# Origin_pi.net
KiCad netlist of a schematic drawn in Altium Designer
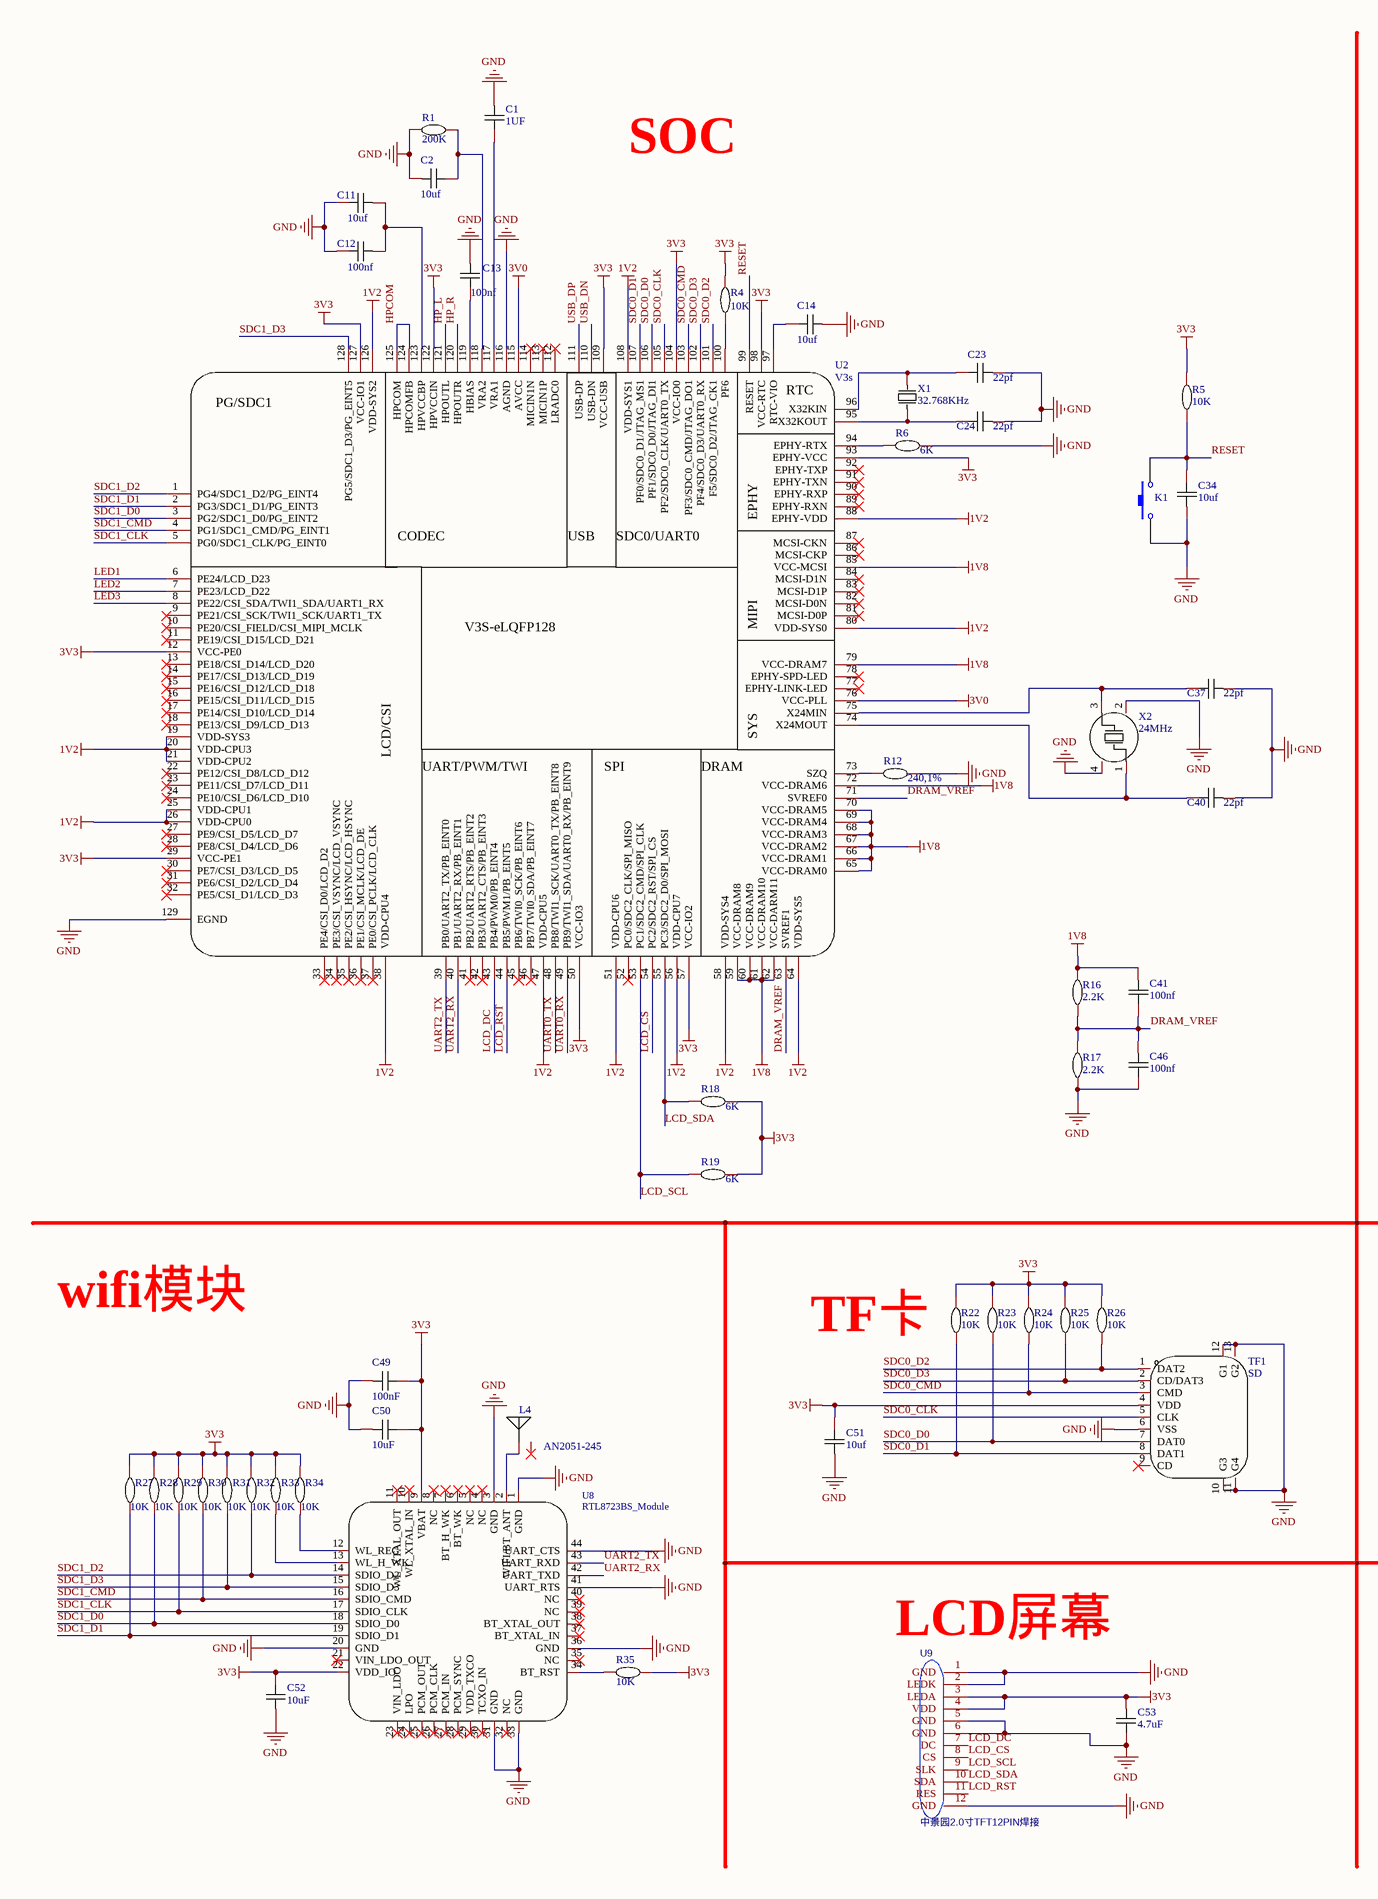
[diagram p0: Origin_pi.SchDoc, left]
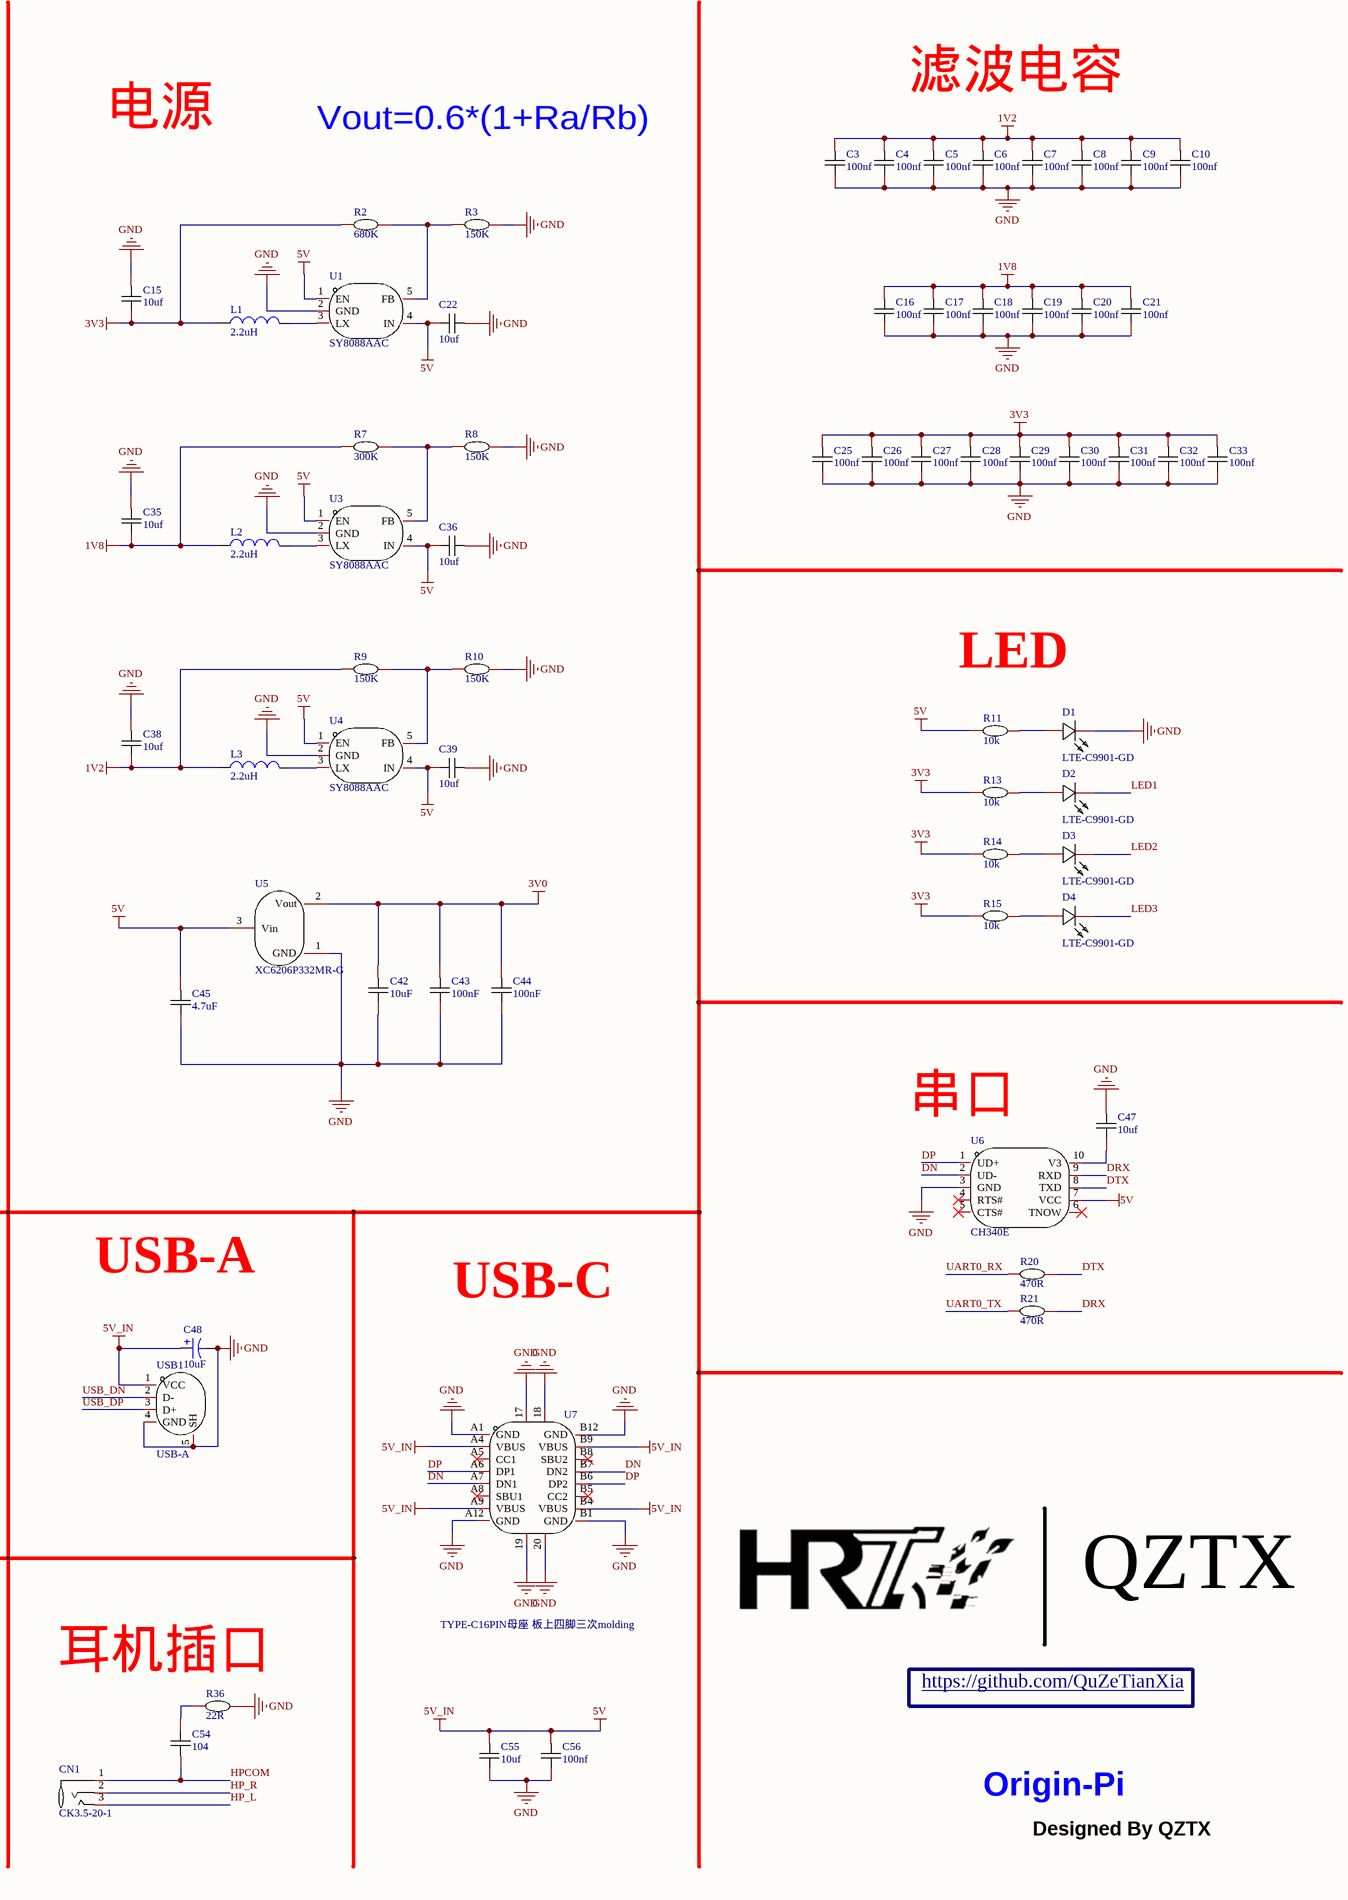
[diagram p1: Origin_pi.SchDoc, right]

(export (version "E")
  (design (tool "Eeschema 10.0.6"))
  (components
    (comp (ref "C1")
      (value "0603DS475K160NT")
      (footprint "C0603:PCBComponent_1")
      (fields (field (name "MANUFACTURER") "FH(风华)") (field (name "NAME") "1UF"))
      (libsource (lib "0603元件") (part "贴片电容0603"))
    )
    (comp (ref "C2")
      (value "0603DS475K160NT")
      (footprint "C0603:PCBComponent_1")
      (fields (field (name "MANUFACTURER") "FH(风华)") (field (name "NAME") "10uf"))
      (libsource (lib "0603元件") (part "贴片电容0603"))
    )
    (comp (ref "C3")
      (value "0603DS475K160NT")
      (footprint "C0603:PCBComponent_1")
      (fields (field (name "MANUFACTURER") "FH(风华)") (field (name "NAME") "100nf"))
      (libsource (lib "0603元件") (part "贴片电容0603"))
    )
    (comp (ref "C4")
      (value "0603DS475K160NT")
      (footprint "C0603:PCBComponent_1")
      (fields (field (name "MANUFACTURER") "FH(风华)") (field (name "NAME") "100nf"))
      (libsource (lib "0603元件") (part "贴片电容0603"))
    )
    (comp (ref "C5")
      (value "0603DS475K160NT")
      (footprint "C0603:PCBComponent_1")
      (fields (field (name "MANUFACTURER") "FH(风华)") (field (name "NAME") "100nf"))
      (libsource (lib "0603元件") (part "贴片电容0603"))
    )
    (comp (ref "C6")
      (value "0603DS475K160NT")
      (footprint "C0603:PCBComponent_1")
      (fields (field (name "MANUFACTURER") "FH(风华)") (field (name "NAME") "100nf"))
      (libsource (lib "0603元件") (part "贴片电容0603"))
    )
    (comp (ref "C7")
      (value "0603DS475K160NT")
      (footprint "C0603:PCBComponent_1")
      (fields (field (name "MANUFACTURER") "FH(风华)") (field (name "NAME") "100nf"))
      (libsource (lib "0603元件") (part "贴片电容0603"))
    )
    (comp (ref "C8")
      (value "0603DS475K160NT")
      (footprint "C0603:PCBComponent_1")
      (fields (field (name "MANUFACTURER") "FH(风华)") (field (name "NAME") "100nf"))
      (libsource (lib "0603元件") (part "贴片电容0603"))
    )
    (comp (ref "C9")
      (value "0603DS475K160NT")
      (footprint "C0603:PCBComponent_1")
      (fields (field (name "MANUFACTURER") "FH(风华)") (field (name "NAME") "100nf"))
      (libsource (lib "0603元件") (part "贴片电容0603"))
    )
    (comp (ref "C10")
      (value "0603DS475K160NT")
      (footprint "C0603:PCBComponent_1")
      (fields (field (name "MANUFACTURER") "FH(风华)") (field (name "NAME") "100nf"))
      (libsource (lib "0603元件") (part "贴片电容0603"))
    )
    (comp (ref "C11")
      (value "0603DS475K160NT")
      (footprint "C0603:PCBComponent_1")
      (fields (field (name "MANUFACTURER") "FH(风华)") (field (name "NAME") "10uf"))
      (libsource (lib "0603元件") (part "贴片电容0603"))
    )
    (comp (ref "C12")
      (value "0603DS475K160NT")
      (footprint "C0603:PCBComponent_1")
      (fields (field (name "MANUFACTURER") "FH(风华)") (field (name "NAME") "100nf"))
      (libsource (lib "0603元件") (part "贴片电容0603"))
    )
    (comp (ref "C13")
      (value "0603DS475K160NT")
      (footprint "C0603:PCBComponent_1")
      (fields (field (name "MANUFACTURER") "FH(风华)") (field (name "NAME") "100nf"))
      (libsource (lib "0603元件") (part "贴片电容0603"))
    )
    (comp (ref "C14")
      (value "0603DS475K160NT")
      (footprint "C0603:PCBComponent_1")
      (fields (field (name "MANUFACTURER") "FH(风华)") (field (name "NAME") "10uf"))
      (libsource (lib "0603元件") (part "贴片电容0603"))
    )
    (comp (ref "C15")
      (value "0603DS475K160NT")
      (footprint "C0603:PCBComponent_1")
      (fields (field (name "MANUFACTURER") "FH(风华)") (field (name "NAME") "10uf"))
      (libsource (lib "0603元件") (part "贴片电容0603"))
    )
    (comp (ref "C16")
      (value "0603DS475K160NT")
      (footprint "C0603:PCBComponent_1")
      (fields (field (name "MANUFACTURER") "FH(风华)") (field (name "NAME") "100nf"))
      (libsource (lib "0603元件") (part "贴片电容0603"))
    )
    (comp (ref "C17")
      (value "0603DS475K160NT")
      (footprint "C0603:PCBComponent_1")
      (fields (field (name "MANUFACTURER") "FH(风华)") (field (name "NAME") "100nf"))
      (libsource (lib "0603元件") (part "贴片电容0603"))
    )
    (comp (ref "C18")
      (value "0603DS475K160NT")
      (footprint "C0603:PCBComponent_1")
      (fields (field (name "MANUFACTURER") "FH(风华)") (field (name "NAME") "100nf"))
      (libsource (lib "0603元件") (part "贴片电容0603"))
    )
    (comp (ref "C19")
      (value "0603DS475K160NT")
      (footprint "C0603:PCBComponent_1")
      (fields (field (name "MANUFACTURER") "FH(风华)") (field (name "NAME") "100nf"))
      (libsource (lib "0603元件") (part "贴片电容0603"))
    )
    (comp (ref "C20")
      (value "0603DS475K160NT")
      (footprint "C0603:PCBComponent_1")
      (fields (field (name "MANUFACTURER") "FH(风华)") (field (name "NAME") "100nf"))
      (libsource (lib "0603元件") (part "贴片电容0603"))
    )
    (comp (ref "C21")
      (value "0603DS475K160NT")
      (footprint "C0603:PCBComponent_1")
      (fields (field (name "MANUFACTURER") "FH(风华)") (field (name "NAME") "100nf"))
      (libsource (lib "0603元件") (part "贴片电容0603"))
    )
    (comp (ref "C22")
      (value "0603DS475K160NT")
      (footprint "C0603:PCBComponent_1")
      (fields (field (name "MANUFACTURER") "FH(风华)") (field (name "NAME") "10uf"))
      (libsource (lib "0603元件") (part "贴片电容0603"))
    )
    (comp (ref "C23")
      (value "0603DS475K160NT")
      (footprint "C0603:PCBComponent_1")
      (fields (field (name "MANUFACTURER") "FH(风华)") (field (name "NAME") "22pf"))
      (libsource (lib "0603元件") (part "贴片电容0603"))
    )
    (comp (ref "C24")
      (value "0603DS475K160NT")
      (footprint "C0603:PCBComponent_1")
      (fields (field (name "MANUFACTURER") "FH(风华)") (field (name "NAME") "22pf"))
      (libsource (lib "0603元件") (part "贴片电容0603"))
    )
    (comp (ref "C25")
      (value "0603DS475K160NT")
      (footprint "C0603:PCBComponent_1")
      (fields (field (name "MANUFACTURER") "FH(风华)") (field (name "NAME") "100nf"))
      (libsource (lib "0603元件") (part "贴片电容0603"))
    )
    (comp (ref "C26")
      (value "0603DS475K160NT")
      (footprint "C0603:PCBComponent_1")
      (fields (field (name "MANUFACTURER") "FH(风华)") (field (name "NAME") "100nf"))
      (libsource (lib "0603元件") (part "贴片电容0603"))
    )
    (comp (ref "C27")
      (value "0603DS475K160NT")
      (footprint "C0603:PCBComponent_1")
      (fields (field (name "MANUFACTURER") "FH(风华)") (field (name "NAME") "100nf"))
      (libsource (lib "0603元件") (part "贴片电容0603"))
    )
    (comp (ref "C28")
      (value "0603DS475K160NT")
      (footprint "C0603:PCBComponent_1")
      (fields (field (name "MANUFACTURER") "FH(风华)") (field (name "NAME") "100nf"))
      (libsource (lib "0603元件") (part "贴片电容0603"))
    )
    (comp (ref "C29")
      (value "0603DS475K160NT")
      (footprint "C0603:PCBComponent_1")
      (fields (field (name "MANUFACTURER") "FH(风华)") (field (name "NAME") "100nf"))
      (libsource (lib "0603元件") (part "贴片电容0603"))
    )
    (comp (ref "C30")
      (value "0603DS475K160NT")
      (footprint "C0603:PCBComponent_1")
      (fields (field (name "MANUFACTURER") "FH(风华)") (field (name "NAME") "100nf"))
      (libsource (lib "0603元件") (part "贴片电容0603"))
    )
    (comp (ref "C31")
      (value "0603DS475K160NT")
      (footprint "C0603:PCBComponent_1")
      (fields (field (name "MANUFACTURER") "FH(风华)") (field (name "NAME") "100nf"))
      (libsource (lib "0603元件") (part "贴片电容0603"))
    )
    (comp (ref "C32")
      (value "0603DS475K160NT")
      (footprint "C0603:PCBComponent_1")
      (fields (field (name "MANUFACTURER") "FH(风华)") (field (name "NAME") "100nf"))
      (libsource (lib "0603元件") (part "贴片电容0603"))
    )
    (comp (ref "C33")
      (value "0603DS475K160NT")
      (footprint "C0603:PCBComponent_1")
      (fields (field (name "MANUFACTURER") "FH(风华)") (field (name "NAME") "100nf"))
      (libsource (lib "0603元件") (part "贴片电容0603"))
    )
    (comp (ref "C34")
      (value "0603DS475K160NT")
      (footprint "C0603:PCBComponent_1")
      (fields (field (name "MANUFACTURER") "FH(风华)") (field (name "NAME") "10uf"))
      (libsource (lib "0603元件") (part "贴片电容0603"))
    )
    (comp (ref "C35")
      (value "0603DS475K160NT")
      (footprint "C0603:PCBComponent_1")
      (fields (field (name "MANUFACTURER") "FH(风华)") (field (name "NAME") "10uf"))
      (libsource (lib "0603元件") (part "贴片电容0603"))
    )
    (comp (ref "C36")
      (value "0603DS475K160NT")
      (footprint "C0603:PCBComponent_1")
      (fields (field (name "MANUFACTURER") "FH(风华)") (field (name "NAME") "10uf"))
      (libsource (lib "0603元件") (part "贴片电容0603"))
    )
    (comp (ref "C37")
      (value "0603DS475K160NT")
      (footprint "C0603:PCBComponent_1")
      (fields (field (name "MANUFACTURER") "FH(风华)") (field (name "NAME") "22pf"))
      (libsource (lib "0603元件") (part "贴片电容0603"))
    )
    (comp (ref "C38")
      (value "0603DS475K160NT")
      (footprint "C0603:PCBComponent_1")
      (fields (field (name "MANUFACTURER") "FH(风华)") (field (name "NAME") "10uf"))
      (libsource (lib "0603元件") (part "贴片电容0603"))
    )
    (comp (ref "C39")
      (value "0603DS475K160NT")
      (footprint "C0603:PCBComponent_1")
      (fields (field (name "MANUFACTURER") "FH(风华)") (field (name "NAME") "10uf"))
      (libsource (lib "0603元件") (part "贴片电容0603"))
    )
    (comp (ref "C40")
      (value "0603DS475K160NT")
      (footprint "C0603:PCBComponent_1")
      (fields (field (name "MANUFACTURER") "FH(风华)") (field (name "NAME") "22pf"))
      (libsource (lib "0603元件") (part "贴片电容0603"))
    )
    (comp (ref "C41")
      (value "0603DS475K160NT")
      (footprint "C0603:PCBComponent_1")
      (fields (field (name "MANUFACTURER") "FH(风华)") (field (name "NAME") "100nf"))
      (libsource (lib "0603元件") (part "贴片电容0603"))
    )
    (comp (ref "C42")
      (value "0603DS475K160NT")
      (footprint "C0603:PCBComponent_1")
      (fields (field (name "MANUFACTURER") "FH(风华)") (field (name "NAME") "10uF"))
      (libsource (lib "0603元件") (part "贴片电容0603"))
    )
    (comp (ref "C43")
      (value "0603DS475K160NT")
      (footprint "C0603:PCBComponent_1")
      (fields (field (name "MANUFACTURER") "FH(风华)") (field (name "NAME") "100nF"))
      (libsource (lib "0603元件") (part "贴片电容0603"))
    )
    (comp (ref "C44")
      (value "0603DS475K160NT")
      (footprint "C0603:PCBComponent_1")
      (fields (field (name "MANUFACTURER") "FH(风华)") (field (name "NAME") "100nF"))
      (libsource (lib "0603元件") (part "贴片电容0603"))
    )
    (comp (ref "C45")
      (value "0603DS475K160NT")
      (footprint "C0603:PCBComponent_1")
      (fields (field (name "MANUFACTURER") "FH(风华)") (field (name "NAME") "4.7uF"))
      (libsource (lib "0603元件") (part "贴片电容0603"))
    )
    (comp (ref "C46")
      (value "0603DS475K160NT")
      (footprint "C0603:PCBComponent_1")
      (fields (field (name "MANUFACTURER") "FH(风华)") (field (name "NAME") "100nf"))
      (libsource (lib "0603元件") (part "贴片电容0603"))
    )
    (comp (ref "C47")
      (value "0603DS475K160NT")
      (footprint "C0603:PCBComponent_1")
      (fields (field (name "MANUFACTURER") "FH(风华)") (field (name "NAME") "10uf"))
      (libsource (lib "0603元件") (part "贴片电容0603"))
    )
    (comp (ref "C48")
      (value "10uF")
      (footprint "CP 3528B")
      (description "极性电容")
      (libsource (lib "ESC_control") (part "Cap_Pol"))
    )
    (comp (ref "C49")
      (value "0603DS475K160NT")
      (footprint "C0603:PCBComponent_1")
      (fields (field (name "MANUFACTURER") "FH(风华)") (field (name "NAME") "100nF"))
      (libsource (lib "0603元件") (part "贴片电容0603"))
    )
    (comp (ref "C50")
      (value "0603DS475K160NT")
      (footprint "C0603:PCBComponent_1")
      (fields (field (name "MANUFACTURER") "FH(风华)") (field (name "NAME") "10uF"))
      (libsource (lib "0603元件") (part "贴片电容0603"))
    )
    (comp (ref "C51")
      (value "0603DS475K160NT")
      (footprint "C0603:PCBComponent_1")
      (fields (field (name "MANUFACTURER") "FH(风华)") (field (name "NAME") "10uf"))
      (libsource (lib "0603元件") (part "贴片电容0603"))
    )
    (comp (ref "C52")
      (value "0603DS475K160NT")
      (footprint "C0603:PCBComponent_1")
      (fields (field (name "MANUFACTURER") "FH(风华)") (field (name "NAME") "10uF"))
      (libsource (lib "0603元件") (part "贴片电容0603"))
    )
    (comp (ref "C53")
      (value "0603DS475K160NT")
      (footprint "C0603:PCBComponent_1")
      (fields (field (name "MANUFACTURER") "FH(风华)") (field (name "NAME") "4.7uF"))
      (libsource (lib "0603元件") (part "贴片电容0603"))
    )
    (comp (ref "C54")
      (value "0603DS475K160NT")
      (footprint "C0603:PCBComponent_1")
      (fields (field (name "MANUFACTURER") "FH(风华)") (field (name "NAME") "104"))
      (libsource (lib "0603元件") (part "贴片电容0603"))
    )
    (comp (ref "C55")
      (value "0603DS475K160NT")
      (footprint "C0603:PCBComponent_1")
      (fields (field (name "MANUFACTURER") "FH(风华)") (field (name "NAME") "10uf"))
      (libsource (lib "0603元件") (part "贴片电容0603"))
    )
    (comp (ref "C56")
      (value "0603DS475K160NT")
      (footprint "C0603:PCBComponent_1")
      (fields (field (name "MANUFACTURER") "FH(风华)") (field (name "NAME") "100nf"))
      (libsource (lib "0603元件") (part "贴片电容0603"))
    )
    (comp (ref "CN1")
      (value "CK3.5-20-1")
      (footprint "AUDIO-SMD_CK3.5-20-1")
      (fields (field (name "MANUFACTURER") "JINJIA(金佳)") (field (name "NAME") "CK3.5-20-1"))
      (libsource (lib "3.5mm耳机接口") (part "CK3.5-20-1"))
    )
    (comp (ref "D1")
      (value "LTE-C9901-GD")
      (footprint "LED0603-RD")
      (fields (field (name "NAME") "LTE-C9901-GD"))
      (libsource (lib "0603元件") (part "LED_0603"))
    )
    (comp (ref "D2")
      (value "LTE-C9901-GD")
      (footprint "LED0603-RD")
      (fields (field (name "NAME") "LTE-C9901-GD"))
      (libsource (lib "0603元件") (part "LED_0603"))
    )
    (comp (ref "D3")
      (value "LTE-C9901-GD")
      (footprint "LED0603-RD")
      (fields (field (name "NAME") "LTE-C9901-GD"))
      (libsource (lib "0603元件") (part "LED_0603"))
    )
    (comp (ref "D4")
      (value "LTE-C9901-GD")
      (footprint "LED0603-RD")
      (fields (field (name "NAME") "LTE-C9901-GD"))
      (libsource (lib "0603元件") (part "LED_0603"))
    )
    (comp (ref "K1")
      (value "Key")
      (footprint "KEY 3.6*2.5 SMD")
      (description "按键")
      (libsource (lib "HRT_D Schlib") (part "Key"))
    )
    (comp (ref "L1")
      (value "2.2uH")
      (footprint "L 0805")
      (description "电感")
      (libsource (lib "HRT_D Schlib") (part "Inductor"))
    )
    (comp (ref "L2")
      (value "2.2uH")
      (footprint "L 0805")
      (description "电感")
      (libsource (lib "HRT_D Schlib") (part "Inductor"))
    )
    (comp (ref "L3")
      (value "2.2uH")
      (footprint "L 0805")
      (description "电感")
      (libsource (lib "HRT_D Schlib") (part "Inductor"))
    )
    (comp (ref "L4")
      (value "AN2051-245")
      (footprint "ANT2051")
      (fields (field (name "MANUFACTURER") "rainsun(霖昱微)") (field (name "NAME") "AN2051-245"))
      (libsource (lib "AN2051-245") (part "AN2051-245"))
    )
    (comp (ref "R1")
      (value "贴片电阻_0603_100K_±1%_1/10W")
      (footprint "PCBComponent_1")
      (fields (field (name "NAME") "200K"))
      (libsource (lib "0603元件") (part "贴片电阻_0603"))
    )
    (comp (ref "R2")
      (value "贴片电阻_0603_100K_±1%_1/10W")
      (footprint "PCBComponent_1")
      (fields (field (name "NAME") "680K"))
      (libsource (lib "0603元件") (part "贴片电阻_0603"))
    )
    (comp (ref "R3")
      (value "贴片电阻_0603_100K_±1%_1/10W")
      (footprint "PCBComponent_1")
      (fields (field (name "NAME") "150K"))
      (libsource (lib "0603元件") (part "贴片电阻_0603"))
    )
    (comp (ref "R4")
      (value "贴片电阻_0603_100K_±1%_1/10W")
      (footprint "PCBComponent_1")
      (fields (field (name "NAME") "10K"))
      (libsource (lib "0603元件") (part "贴片电阻_0603"))
    )
    (comp (ref "R5")
      (value "贴片电阻_0603_100K_±1%_1/10W")
      (footprint "PCBComponent_1")
      (fields (field (name "NAME") "10K"))
      (libsource (lib "0603元件") (part "贴片电阻_0603"))
    )
    (comp (ref "R6")
      (value "贴片电阻_0603_100K_±1%_1/10W")
      (footprint "PCBComponent_1")
      (fields (field (name "NAME") "6K"))
      (libsource (lib "0603元件") (part "贴片电阻_0603"))
    )
    (comp (ref "R7")
      (value "贴片电阻_0603_100K_±1%_1/10W")
      (footprint "PCBComponent_1")
      (fields (field (name "NAME") "300K"))
      (libsource (lib "0603元件") (part "贴片电阻_0603"))
    )
    (comp (ref "R8")
      (value "贴片电阻_0603_100K_±1%_1/10W")
      (footprint "PCBComponent_1")
      (fields (field (name "NAME") "150K"))
      (libsource (lib "0603元件") (part "贴片电阻_0603"))
    )
    (comp (ref "R9")
      (value "贴片电阻_0603_100K_±1%_1/10W")
      (footprint "PCBComponent_1")
      (fields (field (name "NAME") "150K"))
      (libsource (lib "0603元件") (part "贴片电阻_0603"))
    )
    (comp (ref "R10")
      (value "贴片电阻_0603_100K_±1%_1/10W")
      (footprint "PCBComponent_1")
      (fields (field (name "NAME") "150K"))
      (libsource (lib "0603元件") (part "贴片电阻_0603"))
    )
    (comp (ref "R11")
      (value "贴片电阻_0603_100K_±1%_1/10W")
      (footprint "PCBComponent_1")
      (fields (field (name "NAME") "10k"))
      (libsource (lib "0603元件") (part "贴片电阻_0603"))
    )
    (comp (ref "R12")
      (value "贴片电阻_0603_100K_±1%_1/10W")
      (footprint "PCBComponent_1")
      (fields (field (name "NAME") "240,1%"))
      (libsource (lib "0603元件") (part "贴片电阻_0603"))
    )
    (comp (ref "R13")
      (value "贴片电阻_0603_100K_±1%_1/10W")
      (footprint "PCBComponent_1")
      (fields (field (name "NAME") "10k"))
      (libsource (lib "0603元件") (part "贴片电阻_0603"))
    )
    (comp (ref "R14")
      (value "贴片电阻_0603_100K_±1%_1/10W")
      (footprint "PCBComponent_1")
      (fields (field (name "NAME") "10k"))
      (libsource (lib "0603元件") (part "贴片电阻_0603"))
    )
    (comp (ref "R15")
      (value "贴片电阻_0603_100K_±1%_1/10W")
      (footprint "PCBComponent_1")
      (fields (field (name "NAME") "10k"))
      (libsource (lib "0603元件") (part "贴片电阻_0603"))
    )
    (comp (ref "R16")
      (value "贴片电阻_0603_100K_±1%_1/10W")
      (footprint "PCBComponent_1")
      (fields (field (name "NAME") "2.2K"))
      (libsource (lib "0603元件") (part "贴片电阻_0603"))
    )
    (comp (ref "R17")
      (value "贴片电阻_0603_100K_±1%_1/10W")
      (footprint "PCBComponent_1")
      (fields (field (name "NAME") "2.2K"))
      (libsource (lib "0603元件") (part "贴片电阻_0603"))
    )
    (comp (ref "R18")
      (value "贴片电阻_0603_100K_±1%_1/10W")
      (footprint "PCBComponent_1")
      (fields (field (name "NAME") "6K"))
      (libsource (lib "0603元件") (part "贴片电阻_0603"))
    )
    (comp (ref "R19")
      (value "贴片电阻_0603_100K_±1%_1/10W")
      (footprint "PCBComponent_1")
      (fields (field (name "NAME") "6K"))
      (libsource (lib "0603元件") (part "贴片电阻_0603"))
    )
    (comp (ref "R20")
      (value "贴片电阻_0603_100K_±1%_1/10W")
      (footprint "PCBComponent_1")
      (fields (field (name "NAME") "470R"))
      (libsource (lib "0603元件") (part "贴片电阻_0603"))
    )
    (comp (ref "R21")
      (value "贴片电阻_0603_100K_±1%_1/10W")
      (footprint "PCBComponent_1")
      (fields (field (name "NAME") "470R"))
      (libsource (lib "0603元件") (part "贴片电阻_0603"))
    )
    (comp (ref "R22")
      (value "贴片电阻_0603_100K_±1%_1/10W")
      (footprint "PCBComponent_1")
      (fields (field (name "NAME") "10K"))
      (libsource (lib "0603元件") (part "贴片电阻_0603"))
    )
    (comp (ref "R23")
      (value "贴片电阻_0603_100K_±1%_1/10W")
      (footprint "PCBComponent_1")
      (fields (field (name "NAME") "10K"))
      (libsource (lib "0603元件") (part "贴片电阻_0603"))
    )
    (comp (ref "R24")
      (value "贴片电阻_0603_100K_±1%_1/10W")
      (footprint "PCBComponent_1")
      (fields (field (name "NAME") "10K"))
      (libsource (lib "0603元件") (part "贴片电阻_0603"))
    )
    (comp (ref "R25")
      (value "贴片电阻_0603_100K_±1%_1/10W")
      (footprint "PCBComponent_1")
      (fields (field (name "NAME") "10K"))
      (libsource (lib "0603元件") (part "贴片电阻_0603"))
    )
    (comp (ref "R26")
      (value "贴片电阻_0603_100K_±1%_1/10W")
      (footprint "PCBComponent_1")
      (fields (field (name "NAME") "10K"))
      (libsource (lib "0603元件") (part "贴片电阻_0603"))
    )
    (comp (ref "R27")
      (value "贴片电阻_0603_100K_±1%_1/10W")
      (footprint "PCBComponent_1")
      (fields (field (name "NAME") "10K"))
      (libsource (lib "0603元件") (part "贴片电阻_0603"))
    )
    (comp (ref "R28")
      (value "贴片电阻_0603_100K_±1%_1/10W")
      (footprint "PCBComponent_1")
      (fields (field (name "NAME") "10K"))
      (libsource (lib "0603元件") (part "贴片电阻_0603"))
    )
    (comp (ref "R29")
      (value "贴片电阻_0603_100K_±1%_1/10W")
      (footprint "PCBComponent_1")
      (fields (field (name "NAME") "10K"))
      (libsource (lib "0603元件") (part "贴片电阻_0603"))
    )
    (comp (ref "R30")
      (value "贴片电阻_0603_100K_±1%_1/10W")
      (footprint "PCBComponent_1")
      (fields (field (name "NAME") "10K"))
      (libsource (lib "0603元件") (part "贴片电阻_0603"))
    )
    (comp (ref "R31")
      (value "贴片电阻_0603_100K_±1%_1/10W")
      (footprint "PCBComponent_1")
      (fields (field (name "NAME") "10K"))
      (libsource (lib "0603元件") (part "贴片电阻_0603"))
    )
    (comp (ref "R32")
      (value "贴片电阻_0603_100K_±1%_1/10W")
      (footprint "PCBComponent_1")
      (fields (field (name "NAME") "10K"))
      (libsource (lib "0603元件") (part "贴片电阻_0603"))
    )
    (comp (ref "R33")
      (value "贴片电阻_0603_100K_±1%_1/10W")
      (footprint "PCBComponent_1")
      (fields (field (name "NAME") "10K"))
      (libsource (lib "0603元件") (part "贴片电阻_0603"))
    )
    (comp (ref "R34")
      (value "贴片电阻_0603_100K_±1%_1/10W")
      (footprint "PCBComponent_1")
      (fields (field (name "NAME") "10K"))
      (libsource (lib "0603元件") (part "贴片电阻_0603"))
    )
    (comp (ref "R35")
      (value "贴片电阻_0603_100K_±1%_1/10W")
      (footprint "PCBComponent_1")
      (fields (field (name "NAME") "10K"))
      (libsource (lib "0603元件") (part "贴片电阻_0603"))
    )
    (comp (ref "R36")
      (value "贴片电阻_0603_100K_±1%_1/10W")
      (footprint "PCBComponent_1")
      (fields (field (name "NAME") "22R"))
      (libsource (lib "0603元件") (part "贴片电阻_0603"))
    )
    (comp (ref "TF1")
      (value "SD")
      (footprint "TF-SMD_TF-15-15")
      (fields (field (name "NAME") "SD"))
      (libsource (lib "TF卡座") (part "SD"))
    )
    (comp (ref "U1")
      (value "SY8088AAC")
      (footprint "SOT-23-5_L3.0-W1.7-P0.95-LS2.8-BR")
      (fields (field (name "MANUFACTURER") "silergy(矽力杰)") (field (name "NAME") "SY8088AAC"))
      (libsource (lib "SY8088AAC") (part "SY8088AAC"))
    )
    (comp (ref "U2")
      (value "V3s")
      (footprint "LQFP-128_L14.0-W14.0-P0.40-LS16.0-BL-EP5.0")
      (fields (field (name "MANUFACTURER") "Allwinner(全志)") (field (name "NAME") "V3s"))
      (libsource (lib "Allwinner_V3S") (part "Allwinner_V3s"))
    )
    (comp (ref "U3")
      (value "SY8088AAC")
      (footprint "SOT-23-5_L3.0-W1.7-P0.95-LS2.8-BR")
      (fields (field (name "MANUFACTURER") "silergy(矽力杰)") (field (name "NAME") "SY8088AAC"))
      (libsource (lib "SY8088AAC") (part "SY8088AAC"))
    )
    (comp (ref "U4")
      (value "SY8088AAC")
      (footprint "SOT-23-5_L3.0-W1.7-P0.95-LS2.8-BR")
      (fields (field (name "MANUFACTURER") "silergy(矽力杰)") (field (name "NAME") "SY8088AAC"))
      (libsource (lib "SY8088AAC") (part "SY8088AAC"))
    )
    (comp (ref "U5")
      (value "XC6206P332MR-G")
      (footprint "SOT-23-3_L2.9-W1.6-P1.90-LS2.8-BR")
      (fields (field (name "MANUFACTURER") "TOREX(特瑞仕)") (field (name "NAME") "XC6206P332MR-G"))
      (libsource (lib "XC6206") (part "XC6206P332MR-G_C5446"))
    )
    (comp (ref "U6")
      (value "CH340E")
      (footprint "MSOP-10_L3.0-W3.0-P0.50-LS5.0-BL")
      (fields (field (name "MANUFACTURER") "WCH(南京沁恒)") (field (name "NAME") "CH340E"))
      (libsource (lib "CH340E") (part "CH340E"))
    )
    (comp (ref "U7")
      (value "TYPE-C16PIN母座 板上四脚三次molding")
      (footprint "USB-SMD_TYPE-C16PIN")
      (fields (field (name "NAME") "TYPE-C16PIN母座 板上四脚三次molding"))
      (libsource (lib "USB-Type-C-16Pin") (part "TYPE-C16PIN母座 板上四脚三次molding"))
    )
    (comp (ref "U8")
      (value "RTL8723BS_Module")
      (footprint "R8723BS")
      (fields (field (name "NAME") "RTL8723BS_Module"))
      (libsource (lib "RTL8723BS") (part "RTL8723BS"))
    )
    (comp (ref "U9")
      (value "中景园2.0寸TFT12PIN焊接")
      (footprint "PCBComponent_1 - duplicate")
      (fields (field (name "CONTRIBUTOR") "liam_sugar"))
      (libsource (lib "中景园2寸TFT12PIN-st7789v") (part "中景园2.0寸TFT12PIN焊接"))
    )
    (comp (ref "USB1")
      (value "USB-A")
      (footprint "USB-A-TH_SIDE-SINK-USB-A")
      (fields (field (name "NAME") "USB-A"))
      (libsource (lib "USB-A") (part "USB-A"))
    )
    (comp (ref "X1")
      (value "32.768KHz")
      (footprint "2脚3215晶振:OSC-SMD_L3.2-W1.5")
      (fields (field (name "NAME") "32.768KHz"))
      (libsource (lib "2脚3215晶振") (part "32.768KHz_C9900004736"))
    )
    (comp (ref "X2")
      (value "24MHz")
      (footprint "CRYSTAL-SMD_4P-L3.2-W2.5-BL")
      (fields
        (field (name "MANUFACTURER") "YXC(扬兴晶振)")
        (field (name "MANUFACTURER PART") "X322524MSB4SI")
        (field (name "NAME") "24MHz")
      )
      (libsource (lib "4脚3225晶振") (part "X322524MSB4SI"))
    )
  )
  (nets
    (net (code "1") (name "/DN") (class "Default")
      (node (ref "U6") (pin "2") (pinfunction "UD-_2") (pintype "passive"))
      (node (ref "U7") (pin "A7") (pinfunction "DN1_A7") (pintype "passive"))
      (node (ref "U7") (pin "B7") (pinfunction "DN2_B7") (pintype "passive"))
    )
    (net (code "2") (name "/DP") (class "Default")
      (node (ref "U6") (pin "1") (pinfunction "UD+_1") (pintype "passive"))
      (node (ref "U7") (pin "A6") (pinfunction "DP1_A6") (pintype "passive"))
      (node (ref "U7") (pin "B6") (pinfunction "DP2_B6") (pintype "passive"))
    )
    (net (code "3") (name "/DRAM_VREF") (class "Default")
      (node (ref "C41") (pin "1") (pinfunction "1_1") (pintype "passive"))
      (node (ref "C46") (pin "2") (pinfunction "2_2") (pintype "passive"))
      (node (ref "R16") (pin "2") (pinfunction "2_2") (pintype "passive"))
      (node (ref "R17") (pin "1") (pinfunction "1_1") (pintype "passive"))
      (node (ref "U2") (pin "63") (pinfunction "SVREF1_63") (pintype "passive"))
      (node (ref "U2") (pin "71") (pinfunction "SVREF0_71") (pintype "passive"))
    )
    (net (code "4") (name "/DRX") (class "Default")
      (node (ref "R21") (pin "1") (pinfunction "1_1") (pintype "passive"))
      (node (ref "U6") (pin "9") (pinfunction "RXD_9") (pintype "passive"))
    )
    (net (code "5") (name "/DTX") (class "Default")
      (node (ref "R20") (pin "1") (pinfunction "1_1") (pintype "passive"))
      (node (ref "U6") (pin "8") (pinfunction "TXD_8") (pintype "passive"))
    )
    (net (code "6") (name "/HPCOM") (class "Default")
      (node (ref "C54") (pin "2") (pinfunction "2_2") (pintype "passive"))
      (node (ref "CN1") (pin "1") (pinfunction "1_1") (pintype "passive"))
      (node (ref "U2") (pin "124") (pinfunction "HPCOMFB_124") (pintype "passive"))
      (node (ref "U2") (pin "125") (pinfunction "HPCOM_125") (pintype "passive"))
    )
    (net (code "7") (name "/HP_L") (class "Default")
      (node (ref "CN1") (pin "3") (pinfunction "3_3") (pintype "passive"))
      (node (ref "U2") (pin "121") (pinfunction "HPOUTL_121") (pintype "passive"))
    )
    (net (code "8") (name "/HP_R") (class "Default")
      (node (ref "CN1") (pin "2") (pinfunction "2_2") (pintype "passive"))
      (node (ref "U2") (pin "120") (pinfunction "HPOUTR_120") (pintype "passive"))
    )
    (net (code "9") (name "/LCD_CS") (class "Default")
      (node (ref "U2") (pin "54") (pinfunction "PC2/SDC2_RST/SPI_CS_54") (pintype "passive"))
      (node (ref "U9") (pin "8") (pinfunction "CS_8") (pintype "passive"))
    )
    (net (code "10") (name "/LCD_DC") (class "Default")
      (node (ref "U2") (pin "43") (pinfunction "PB4/PWM0/PB_EINT4_43") (pintype "passive"))
      (node (ref "U9") (pin "7") (pinfunction "DC_7") (pintype "passive"))
    )
    (net (code "11") (name "/LCD_RST") (class "Default")
      (node (ref "U2") (pin "44") (pinfunction "PB5/PWM1/PB_EINT5_44") (pintype "passive"))
      (node (ref "U9") (pin "11") (pinfunction "RES_11") (pintype "passive"))
    )
    (net (code "12") (name "/LCD_SCL") (class "Default")
      (node (ref "R19") (pin "2") (pinfunction "2_2") (pintype "passive"))
      (node (ref "U2") (pin "53") (pinfunction "PC1/SDC2_CMD/SPI_CLK_53") (pintype "passive"))
      (node (ref "U9") (pin "9") (pinfunction "SLK_9") (pintype "passive"))
    )
    (net (code "13") (name "/LCD_SDA") (class "Default")
      (node (ref "R18") (pin "2") (pinfunction "2_2") (pintype "passive"))
      (node (ref "U2") (pin "55") (pinfunction "PC3/SDC2_D0/SPI_MOSI_55") (pintype "passive"))
      (node (ref "U9") (pin "10") (pinfunction "SDA_10") (pintype "passive"))
    )
    (net (code "14") (name "/LED1") (class "Default")
      (node (ref "D2") (pin "1") (pinfunction "-_1") (pintype "passive"))
      (node (ref "U2") (pin "6") (pinfunction "PE24/LCD_D23_6") (pintype "passive"))
    )
    (net (code "15") (name "/LED2") (class "Default")
      (node (ref "D3") (pin "1") (pinfunction "-_1") (pintype "passive"))
      (node (ref "U2") (pin "7") (pinfunction "PE23/LCD_D22_7") (pintype "passive"))
    )
    (net (code "16") (name "/LED3") (class "Default")
      (node (ref "D4") (pin "1") (pinfunction "-_1") (pintype "passive"))
      (node (ref "U2") (pin "8") (pinfunction "PE22/CSI_SDA/TWI1_SDA/UART1_RX_8") (pintype "passive"))
    )
    (net (code "17") (name "/RESET") (class "Default")
      (node (ref "C34") (pin "1") (pinfunction "1_1") (pintype "passive"))
      (node (ref "K1") (pin "2") (pinfunction "2_2") (pintype "passive"))
      (node (ref "R5") (pin "1") (pinfunction "1_1") (pintype "passive"))
      (node (ref "U2") (pin "99") (pinfunction "RESET_99") (pintype "passive"))
    )
    (net (code "18") (name "/SDC0_CLK") (class "Default")
      (node (ref "TF1") (pin "5") (pinfunction "CLK_5") (pintype "passive"))
      (node (ref "U2") (pin "105") (pinfunction "PF2/SDC0_CLK/UART0_TX_105") (pintype "passive"))
    )
    (net (code "19") (name "/SDC0_CMD") (class "Default")
      (node (ref "R24") (pin "2") (pinfunction "2_2") (pintype "passive"))
      (node (ref "TF1") (pin "3") (pinfunction "CMD_3") (pintype "passive"))
      (node (ref "U2") (pin "103") (pinfunction "PF3/SDC0_CMD/JTAG_DO1_103") (pintype "passive"))
    )
    (net (code "20") (name "/SDC0_D0") (class "Default")
      (node (ref "R23") (pin "2") (pinfunction "2_2") (pintype "passive"))
      (node (ref "TF1") (pin "7") (pinfunction "DAT0_7") (pintype "passive"))
      (node (ref "U2") (pin "106") (pinfunction "PF1/SDC0_D0/JTAG_DI1_106") (pintype "passive"))
    )
    (net (code "21") (name "/SDC0_D1") (class "Default")
      (node (ref "R22") (pin "2") (pinfunction "2_2") (pintype "passive"))
      (node (ref "TF1") (pin "8") (pinfunction "DAT1_8") (pintype "passive"))
      (node (ref "U2") (pin "107") (pinfunction "PF0/SDC0_D1/JTAG_MS1_107") (pintype "passive"))
    )
    (net (code "22") (name "/SDC0_D2") (class "Default")
      (node (ref "R26") (pin "2") (pinfunction "2_2") (pintype "passive"))
      (node (ref "TF1") (pin "1") (pinfunction "DAT2_1") (pintype "passive"))
      (node (ref "U2") (pin "101") (pinfunction "F5/SDC0_D2/JTAG_CK1_101") (pintype "passive"))
    )
    (net (code "23") (name "/SDC0_D3") (class "Default")
      (node (ref "R25") (pin "2") (pinfunction "2_2") (pintype "passive"))
      (node (ref "TF1") (pin "2") (pinfunction "CD/DAT3_2") (pintype "passive"))
      (node (ref "U2") (pin "102") (pinfunction "PF4/SDC0_D3/UART0_RX_102") (pintype "passive"))
    )
    (net (code "24") (name "/SDC1_CLK") (class "Default")
      (node (ref "R29") (pin "2") (pinfunction "2_2") (pintype "passive"))
      (node (ref "U2") (pin "5") (pinfunction "PG0/SDC1_CLK/PG_EINT0_5") (pintype "passive"))
      (node (ref "U8") (pin "17") (pinfunction "SDIO_CLK_17") (pintype "passive"))
    )
    (net (code "25") (name "/SDC1_CMD") (class "Default")
      (node (ref "R30") (pin "2") (pinfunction "2_2") (pintype "passive"))
      (node (ref "U2") (pin "4") (pinfunction "PG1/SDC1_CMD/PG_EINT1_4") (pintype "passive"))
      (node (ref "U8") (pin "16") (pinfunction "SDIO_CMD_16") (pintype "passive"))
    )
    (net (code "26") (name "/SDC1_D0") (class "Default")
      (node (ref "R28") (pin "2") (pinfunction "2_2") (pintype "passive"))
      (node (ref "U2") (pin "3") (pinfunction "PG2/SDC1_D0/PG_EINT2_3") (pintype "passive"))
      (node (ref "U8") (pin "18") (pinfunction "SDIO_D0_18") (pintype "passive"))
    )
    (net (code "27") (name "/SDC1_D1") (class "Default")
      (node (ref "R27") (pin "2") (pinfunction "2_2") (pintype "passive"))
      (node (ref "U2") (pin "2") (pinfunction "PG3/SDC1_D1/PG_EINT3_2") (pintype "passive"))
      (node (ref "U8") (pin "19") (pinfunction "SDIO_D1_19") (pintype "passive"))
    )
    (net (code "28") (name "/SDC1_D2") (class "Default")
      (node (ref "R32") (pin "2") (pinfunction "2_2") (pintype "passive"))
      (node (ref "U2") (pin "1") (pinfunction "PG4/SDC1_D2/PG_EINT4_1") (pintype "passive"))
      (node (ref "U8") (pin "14") (pinfunction "SDIO_D2_14") (pintype "passive"))
    )
    (net (code "29") (name "/SDC1_D3") (class "Default")
      (node (ref "R31") (pin "2") (pinfunction "2_2") (pintype "passive"))
      (node (ref "U2") (pin "128") (pinfunction "PG5/SDC1_D3/PG_EINT5_128") (pintype "passive"))
      (node (ref "U8") (pin "15") (pinfunction "SDIO_D3_15") (pintype "passive"))
    )
    (net (code "30") (name "/UART0_RX") (class "Default")
      (node (ref "R20") (pin "2") (pinfunction "2_2") (pintype "passive"))
      (node (ref "U2") (pin "49") (pinfunction "PB9/TWI1_SDA/UART0_RX/PB_EINT9_49") (pintype "passive"))
    )
    (net (code "31") (name "/UART0_TX") (class "Default")
      (node (ref "R21") (pin "2") (pinfunction "2_2") (pintype "passive"))
      (node (ref "U2") (pin "48") (pinfunction "PB8/TWI1_SCK/UART0_TX/PB_EINT8_48") (pintype "passive"))
    )
    (net (code "32") (name "/UART2_RX") (class "Default")
      (node (ref "U2") (pin "40") (pinfunction "PB1/UART2_RX/PB_EINT1_40") (pintype "passive"))
      (node (ref "U8") (pin "42") (pinfunction "UART_TXD_42") (pintype "passive"))
    )
    (net (code "33") (name "/UART2_TX") (class "Default")
      (node (ref "U2") (pin "39") (pinfunction "PB0/UART2_TX/PB_EINT0_39") (pintype "passive"))
      (node (ref "U8") (pin "43") (pinfunction "UART_RXD_43") (pintype "passive"))
    )
    (net (code "34") (name "/USB_DN") (class "Default")
      (node (ref "U2") (pin "110") (pinfunction "USB-DN_110") (pintype "passive"))
      (node (ref "USB1") (pin "2") (pinfunction "D-_2") (pintype "passive"))
    )
    (net (code "35") (name "/USB_DP") (class "Default")
      (node (ref "U2") (pin "111") (pinfunction "USB-DP_111") (pintype "passive"))
      (node (ref "USB1") (pin "3") (pinfunction "D+_3") (pintype "passive"))
    )
    (net (code "36") (name "1V2") (class "Default")
      (node (ref "C10") (pin "2") (pinfunction "2_2") (pintype "passive"))
      (node (ref "C3") (pin "2") (pinfunction "2_2") (pintype "passive"))
      (node (ref "C38") (pin "1") (pinfunction "1_1") (pintype "passive"))
      (node (ref "C4") (pin "2") (pinfunction "2_2") (pintype "passive"))
      (node (ref "C5") (pin "2") (pinfunction "2_2") (pintype "passive"))
      (node (ref "C6") (pin "2") (pinfunction "2_2") (pintype "passive"))
      (node (ref "C7") (pin "2") (pinfunction "2_2") (pintype "passive"))
      (node (ref "C8") (pin "2") (pinfunction "2_2") (pintype "passive"))
      (node (ref "C9") (pin "2") (pinfunction "2_2") (pintype "passive"))
      (node (ref "L3") (pin "1") (pinfunction "1_1") (pintype "passive"))
      (node (ref "R9") (pin "2") (pinfunction "2_2") (pintype "passive"))
      (node (ref "U2") (pin "108") (pinfunction "VDD-SYS1_108") (pintype "passive"))
      (node (ref "U2") (pin "126") (pinfunction "VDD-SYS2_126") (pintype "passive"))
      (node (ref "U2") (pin "19") (pinfunction "VDD-SYS3_19") (pintype "passive"))
      (node (ref "U2") (pin "20") (pinfunction "VDD-CPU3_20") (pintype "passive"))
      (node (ref "U2") (pin "21") (pinfunction "VDD-CPU2_21") (pintype "passive"))
      (node (ref "U2") (pin "25") (pinfunction "VDD-CPU1_25") (pintype "passive"))
      (node (ref "U2") (pin "26") (pinfunction "VDD-CPU0_26") (pintype "passive"))
      (node (ref "U2") (pin "38") (pinfunction "VDD-CPU4_38") (pintype "passive"))
      (node (ref "U2") (pin "47") (pinfunction "VDD-CPU5_47") (pintype "passive"))
      (node (ref "U2") (pin "51") (pinfunction "VDD-CPU6_51") (pintype "passive"))
      (node (ref "U2") (pin "56") (pinfunction "VDD-CPU7_56") (pintype "passive"))
      (node (ref "U2") (pin "58") (pinfunction "VDD-SYS4_58") (pintype "passive"))
      (node (ref "U2") (pin "64") (pinfunction "VDD-SYS5_64") (pintype "passive"))
      (node (ref "U2") (pin "80") (pinfunction "VDD-SYS0_80") (pintype "passive"))
      (node (ref "U2") (pin "88") (pinfunction "EPHY-VDD_88") (pintype "passive"))
    )
    (net (code "37") (name "1V8") (class "Default")
      (node (ref "C16") (pin "2") (pinfunction "2_2") (pintype "passive"))
      (node (ref "C17") (pin "2") (pinfunction "2_2") (pintype "passive"))
      (node (ref "C18") (pin "2") (pinfunction "2_2") (pintype "passive"))
      (node (ref "C19") (pin "2") (pinfunction "2_2") (pintype "passive"))
      (node (ref "C20") (pin "2") (pinfunction "2_2") (pintype "passive"))
      (node (ref "C21") (pin "2") (pinfunction "2_2") (pintype "passive"))
      (node (ref "C35") (pin "1") (pinfunction "1_1") (pintype "passive"))
      (node (ref "C41") (pin "2") (pinfunction "2_2") (pintype "passive"))
      (node (ref "L2") (pin "1") (pinfunction "1_1") (pintype "passive"))
      (node (ref "R16") (pin "1") (pinfunction "1_1") (pintype "passive"))
      (node (ref "R7") (pin "2") (pinfunction "2_2") (pintype "passive"))
      (node (ref "U2") (pin "59") (pinfunction "VCC-DRAM8_59") (pintype "passive"))
      (node (ref "U2") (pin "60") (pinfunction "VCC-DRAM9_60") (pintype "passive"))
      (node (ref "U2") (pin "61") (pinfunction "VCC-DRAM10_61") (pintype "passive"))
      (node (ref "U2") (pin "62") (pinfunction "VCC-DARM11_62") (pintype "passive"))
      (node (ref "U2") (pin "65") (pinfunction "VCC-DRAM0_65") (pintype "passive"))
      (node (ref "U2") (pin "66") (pinfunction "VCC-DRAM1_66") (pintype "passive"))
      (node (ref "U2") (pin "67") (pinfunction "VCC-DRAM2_67") (pintype "passive"))
      (node (ref "U2") (pin "68") (pinfunction "VCC-DRAM3_68") (pintype "passive"))
      (node (ref "U2") (pin "69") (pinfunction "VCC-DRAM4_69") (pintype "passive"))
      (node (ref "U2") (pin "70") (pinfunction "VCC-DRAM5_70") (pintype "passive"))
      (node (ref "U2") (pin "72") (pinfunction "VCC-DRAM6_72") (pintype "passive"))
      (node (ref "U2") (pin "79") (pinfunction "VCC-DRAM7_79") (pintype "passive"))
      (node (ref "U2") (pin "85") (pinfunction "VCC-MCSI_85") (pintype "passive"))
    )
    (net (code "38") (name "3V0") (class "Default")
      (node (ref "C42") (pin "2") (pinfunction "2_2") (pintype "passive"))
      (node (ref "C43") (pin "2") (pinfunction "2_2") (pintype "passive"))
      (node (ref "C44") (pin "2") (pinfunction "2_2") (pintype "passive"))
      (node (ref "U2") (pin "115") (pinfunction "AVCC_115") (pintype "passive"))
      (node (ref "U2") (pin "76") (pinfunction "VCC-PLL_76") (pintype "passive"))
      (node (ref "U5") (pin "2") (pinfunction "Vout_2") (pintype "passive"))
    )
    (net (code "39") (name "3V3") (class "Default")
      (node (ref "C15") (pin "1") (pinfunction "1_1") (pintype "passive"))
      (node (ref "C25") (pin "2") (pinfunction "2_2") (pintype "passive"))
      (node (ref "C26") (pin "2") (pinfunction "2_2") (pintype "passive"))
      (node (ref "C27") (pin "2") (pinfunction "2_2") (pintype "passive"))
      (node (ref "C28") (pin "2") (pinfunction "2_2") (pintype "passive"))
      (node (ref "C29") (pin "2") (pinfunction "2_2") (pintype "passive"))
      (node (ref "C30") (pin "2") (pinfunction "2_2") (pintype "passive"))
      (node (ref "C31") (pin "2") (pinfunction "2_2") (pintype "passive"))
      (node (ref "C32") (pin "2") (pinfunction "2_2") (pintype "passive"))
      (node (ref "C33") (pin "2") (pinfunction "2_2") (pintype "passive"))
      (node (ref "C49") (pin "1") (pinfunction "1_1") (pintype "passive"))
      (node (ref "C50") (pin "1") (pinfunction "1_1") (pintype "passive"))
      (node (ref "C51") (pin "1") (pinfunction "1_1") (pintype "passive"))
      (node (ref "C52") (pin "1") (pinfunction "1_1") (pintype "passive"))
      (node (ref "C53") (pin "2") (pinfunction "2_2") (pintype "passive"))
      (node (ref "L1") (pin "1") (pinfunction "1_1") (pintype "passive"))
      (node (ref "R13") (pin "2") (pinfunction "2_2") (pintype "passive"))
      (node (ref "R14") (pin "2") (pinfunction "2_2") (pintype "passive"))
      (node (ref "R15") (pin "2") (pinfunction "2_2") (pintype "passive"))
      (node (ref "R18") (pin "1") (pinfunction "1_1") (pintype "passive"))
      (node (ref "R19") (pin "1") (pinfunction "1_1") (pintype "passive"))
      (node (ref "R2") (pin "2") (pinfunction "2_2") (pintype "passive"))
      (node (ref "R22") (pin "1") (pinfunction "1_1") (pintype "passive"))
      (node (ref "R23") (pin "1") (pinfunction "1_1") (pintype "passive"))
      (node (ref "R24") (pin "1") (pinfunction "1_1") (pintype "passive"))
      (node (ref "R25") (pin "1") (pinfunction "1_1") (pintype "passive"))
      (node (ref "R26") (pin "1") (pinfunction "1_1") (pintype "passive"))
      (node (ref "R27") (pin "1") (pinfunction "1_1") (pintype "passive"))
      (node (ref "R28") (pin "1") (pinfunction "1_1") (pintype "passive"))
      (node (ref "R29") (pin "1") (pinfunction "1_1") (pintype "passive"))
      (node (ref "R30") (pin "1") (pinfunction "1_1") (pintype "passive"))
      (node (ref "R31") (pin "1") (pinfunction "1_1") (pintype "passive"))
      (node (ref "R32") (pin "1") (pinfunction "1_1") (pintype "passive"))
      (node (ref "R33") (pin "1") (pinfunction "1_1") (pintype "passive"))
      (node (ref "R34") (pin "1") (pinfunction "1_1") (pintype "passive"))
      (node (ref "R35") (pin "1") (pinfunction "1_1") (pintype "passive"))
      (node (ref "R4") (pin "2") (pinfunction "2_2") (pintype "passive"))
      (node (ref "R5") (pin "2") (pinfunction "2_2") (pintype "passive"))
      (node (ref "TF1") (pin "4") (pinfunction "VDD_4") (pintype "passive"))
      (node (ref "U2") (pin "104") (pinfunction "VCC-IO0_104") (pintype "passive"))
      (node (ref "U2") (pin "109") (pinfunction "VCC-USB_109") (pintype "passive"))
      (node (ref "U2") (pin "12") (pinfunction "VCC-PE0_12") (pintype "passive"))
      (node (ref "U2") (pin "122") (pinfunction "HPVCCIN_122") (pintype "passive"))
      (node (ref "U2") (pin "127") (pinfunction "VCC-IO1_127") (pintype "passive"))
      (node (ref "U2") (pin "29") (pinfunction "VCC-PE1_29") (pintype "passive"))
      (node (ref "U2") (pin "50") (pinfunction "VCC-IO3_50") (pintype "passive"))
      (node (ref "U2") (pin "57") (pinfunction "VCC-IO2_57") (pintype "passive"))
      (node (ref "U2") (pin "93") (pinfunction "EPHY-VCC_93") (pintype "passive"))
      (node (ref "U2") (pin "98") (pinfunction "VCC-RTC_98") (pintype "passive"))
      (node (ref "U8") (pin "22") (pinfunction "VDD_IO_22") (pintype "passive"))
      (node (ref "U8") (pin "9") (pinfunction "VBAT_9") (pintype "passive"))
      (node (ref "U9") (pin "3") (pinfunction "LEDA_3") (pintype "passive"))
      (node (ref "U9") (pin "4") (pinfunction "VDD_4") (pintype "passive"))
    )
    (net (code "40") (name "5V") (class "Default")
      (node (ref "C22") (pin "1") (pinfunction "1_1") (pintype "passive"))
      (node (ref "C36") (pin "1") (pinfunction "1_1") (pintype "passive"))
      (node (ref "C39") (pin "1") (pinfunction "1_1") (pintype "passive"))
      (node (ref "C45") (pin "2") (pinfunction "2_2") (pintype "passive"))
      (node (ref "C48") (pin "1") (pinfunction "1_1") (pintype "passive"))
      (node (ref "C55") (pin "2") (pinfunction "2_2") (pintype "passive"))
      (node (ref "C56") (pin "2") (pinfunction "2_2") (pintype "passive"))
      (node (ref "R11") (pin "2") (pinfunction "2_2") (pintype "passive"))
      (node (ref "U1") (pin "1") (pinfunction "EN_1") (pintype "passive"))
      (node (ref "U1") (pin "4") (pinfunction "IN_4") (pintype "passive"))
      (node (ref "U3") (pin "1") (pinfunction "EN_1") (pintype "passive"))
      (node (ref "U3") (pin "4") (pinfunction "IN_4") (pintype "passive"))
      (node (ref "U4") (pin "1") (pinfunction "EN_1") (pintype "passive"))
      (node (ref "U4") (pin "4") (pinfunction "IN_4") (pintype "passive"))
      (node (ref "U5") (pin "3") (pinfunction "Vin_3") (pintype "passive"))
      (node (ref "U6") (pin "7") (pinfunction "VCC_7") (pintype "passive"))
      (node (ref "U7") (pin "A4") (pinfunction "VBUS_A4") (pintype "passive"))
      (node (ref "U7") (pin "A9") (pinfunction "VBUS_A9") (pintype "passive"))
      (node (ref "U7") (pin "B4") (pinfunction "VBUS_B4") (pintype "passive"))
      (node (ref "U7") (pin "B9") (pinfunction "VBUS_B9") (pintype "passive"))
      (node (ref "USB1") (pin "1") (pinfunction "VCC_1") (pintype "passive"))
    )
    (net (code "41") (name "GND") (class "Default")
      (node (ref "C1") (pin "2") (pinfunction "2_2") (pintype "passive"))
      (node (ref "C10") (pin "1") (pinfunction "1_1") (pintype "passive"))
      (node (ref "C11") (pin "1") (pinfunction "1_1") (pintype "passive"))
      (node (ref "C12") (pin "1") (pinfunction "1_1") (pintype "passive"))
      (node (ref "C13") (pin "2") (pinfunction "2_2") (pintype "passive"))
      (node (ref "C14") (pin "2") (pinfunction "2_2") (pintype "passive"))
      (node (ref "C15") (pin "2") (pinfunction "2_2") (pintype "passive"))
      (node (ref "C16") (pin "1") (pinfunction "1_1") (pintype "passive"))
      (node (ref "C17") (pin "1") (pinfunction "1_1") (pintype "passive"))
      (node (ref "C18") (pin "1") (pinfunction "1_1") (pintype "passive"))
      (node (ref "C19") (pin "1") (pinfunction "1_1") (pintype "passive"))
      (node (ref "C2") (pin "2") (pinfunction "2_2") (pintype "passive"))
      (node (ref "C20") (pin "1") (pinfunction "1_1") (pintype "passive"))
      (node (ref "C21") (pin "1") (pinfunction "1_1") (pintype "passive"))
      (node (ref "C22") (pin "2") (pinfunction "2_2") (pintype "passive"))
      (node (ref "C23") (pin "2") (pinfunction "2_2") (pintype "passive"))
      (node (ref "C24") (pin "2") (pinfunction "2_2") (pintype "passive"))
      (node (ref "C25") (pin "1") (pinfunction "1_1") (pintype "passive"))
      (node (ref "C26") (pin "1") (pinfunction "1_1") (pintype "passive"))
      (node (ref "C27") (pin "1") (pinfunction "1_1") (pintype "passive"))
      (node (ref "C28") (pin "1") (pinfunction "1_1") (pintype "passive"))
      (node (ref "C29") (pin "1") (pinfunction "1_1") (pintype "passive"))
      (node (ref "C3") (pin "1") (pinfunction "1_1") (pintype "passive"))
      (node (ref "C30") (pin "1") (pinfunction "1_1") (pintype "passive"))
      (node (ref "C31") (pin "1") (pinfunction "1_1") (pintype "passive"))
      (node (ref "C32") (pin "1") (pinfunction "1_1") (pintype "passive"))
      (node (ref "C33") (pin "1") (pinfunction "1_1") (pintype "passive"))
      (node (ref "C34") (pin "2") (pinfunction "2_2") (pintype "passive"))
      (node (ref "C35") (pin "2") (pinfunction "2_2") (pintype "passive"))
      (node (ref "C36") (pin "2") (pinfunction "2_2") (pintype "passive"))
      (node (ref "C37") (pin "2") (pinfunction "2_2") (pintype "passive"))
      (node (ref "C38") (pin "2") (pinfunction "2_2") (pintype "passive"))
      (node (ref "C39") (pin "2") (pinfunction "2_2") (pintype "passive"))
      (node (ref "C4") (pin "1") (pinfunction "1_1") (pintype "passive"))
      (node (ref "C40") (pin "2") (pinfunction "2_2") (pintype "passive"))
      (node (ref "C42") (pin "1") (pinfunction "1_1") (pintype "passive"))
      (node (ref "C43") (pin "1") (pinfunction "1_1") (pintype "passive"))
      (node (ref "C44") (pin "1") (pinfunction "1_1") (pintype "passive"))
      (node (ref "C45") (pin "1") (pinfunction "1_1") (pintype "passive"))
      (node (ref "C46") (pin "1") (pinfunction "1_1") (pintype "passive"))
      (node (ref "C47") (pin "2") (pinfunction "2_2") (pintype "passive"))
      (node (ref "C48") (pin "2") (pinfunction "2_2") (pintype "passive"))
      (node (ref "C49") (pin "2") (pinfunction "2_2") (pintype "passive"))
      (node (ref "C5") (pin "1") (pinfunction "1_1") (pintype "passive"))
      (node (ref "C50") (pin "2") (pinfunction "2_2") (pintype "passive"))
      (node (ref "C51") (pin "2") (pinfunction "2_2") (pintype "passive"))
      (node (ref "C52") (pin "2") (pinfunction "2_2") (pintype "passive"))
      (node (ref "C53") (pin "1") (pinfunction "1_1") (pintype "passive"))
      (node (ref "C55") (pin "1") (pinfunction "1_1") (pintype "passive"))
      (node (ref "C56") (pin "1") (pinfunction "1_1") (pintype "passive"))
      (node (ref "C6") (pin "1") (pinfunction "1_1") (pintype "passive"))
      (node (ref "C7") (pin "1") (pinfunction "1_1") (pintype "passive"))
      (node (ref "C8") (pin "1") (pinfunction "1_1") (pintype "passive"))
      (node (ref "C9") (pin "1") (pinfunction "1_1") (pintype "passive"))
      (node (ref "D1") (pin "1") (pinfunction "-_1") (pintype "passive"))
      (node (ref "K1") (pin "1") (pinfunction "1_1") (pintype "passive"))
      (node (ref "R1") (pin "2") (pinfunction "2_2") (pintype "passive"))
      (node (ref "R10") (pin "1") (pinfunction "1_1") (pintype "passive"))
      (node (ref "R12") (pin "1") (pinfunction "1_1") (pintype "passive"))
      (node (ref "R17") (pin "2") (pinfunction "2_2") (pintype "passive"))
      (node (ref "R3") (pin "1") (pinfunction "1_1") (pintype "passive"))
      (node (ref "R36") (pin "1") (pinfunction "1_1") (pintype "passive"))
      (node (ref "R6") (pin "1") (pinfunction "1_1") (pintype "passive"))
      (node (ref "R8") (pin "1") (pinfunction "1_1") (pintype "passive"))
      (node (ref "TF1") (pin "10") (pinfunction "G3_10") (pintype "passive"))
      (node (ref "TF1") (pin "11") (pinfunction "G4_11") (pintype "passive"))
      (node (ref "TF1") (pin "12") (pinfunction "G1_12") (pintype "passive"))
      (node (ref "TF1") (pin "13") (pinfunction "G2_13") (pintype "passive"))
      (node (ref "TF1") (pin "6") (pinfunction "VSS_6") (pintype "passive"))
      (node (ref "U1") (pin "2") (pinfunction "GND_2") (pintype "passive"))
      (node (ref "U2") (pin "116") (pinfunction "AGND_116") (pintype "passive"))
      (node (ref "U2") (pin "129") (pinfunction "EGND_129") (pintype "passive"))
      (node (ref "U3") (pin "2") (pinfunction "GND_2") (pintype "passive"))
      (node (ref "U4") (pin "2") (pinfunction "GND_2") (pintype "passive"))
      (node (ref "U5") (pin "1") (pinfunction "GND_1") (pintype "passive"))
      (node (ref "U6") (pin "3") (pinfunction "GND_3") (pintype "passive"))
      (node (ref "U7") (pin "17") (pinfunction "17_17") (pintype "passive"))
      (node (ref "U7") (pin "18") (pinfunction "18_18") (pintype "passive"))
      (node (ref "U7") (pin "19") (pinfunction "19_19") (pintype "passive"))
      (node (ref "U7") (pin "20") (pinfunction "20_20") (pintype "passive"))
      (node (ref "U7") (pin "A1") (pinfunction "GND_A1") (pintype "passive"))
      (node (ref "U7") (pin "A12") (pinfunction "GND_A12") (pintype "passive"))
      (node (ref "U7") (pin "B1") (pinfunction "GND_B1") (pintype "passive"))
      (node (ref "U7") (pin "B12") (pinfunction "GND_B12") (pintype "passive"))
      (node (ref "U8") (pin "1") (pinfunction "GND_1") (pintype "passive"))
      (node (ref "U8") (pin "20") (pinfunction "GND_20") (pintype "passive"))
      (node (ref "U8") (pin "3") (pinfunction "GND_3") (pintype "passive"))
      (node (ref "U8") (pin "31") (pinfunction "GND_31") (pintype "passive"))
      (node (ref "U8") (pin "33") (pinfunction "GND_33") (pintype "passive"))
      (node (ref "U8") (pin "36") (pinfunction "GND_36") (pintype "passive"))
      (node (ref "U8") (pin "41") (pinfunction "UART_RTS_41") (pintype "passive"))
      (node (ref "U8") (pin "44") (pinfunction "UART_CTS_44") (pintype "passive"))
      (node (ref "U9") (pin "1") (pinfunction "GND_1") (pintype "passive"))
      (node (ref "U9") (pin "12") (pinfunction "GND_12") (pintype "passive"))
      (node (ref "U9") (pin "2") (pinfunction "LEDK_2") (pintype "passive"))
      (node (ref "U9") (pin "5") (pinfunction "GND_5") (pintype "passive"))
      (node (ref "U9") (pin "6") (pinfunction "GND_6") (pintype "passive"))
      (node (ref "USB1") (pin "4") (pinfunction "GND_4") (pintype "passive"))
      (node (ref "USB1") (pin "5") (pinfunction "SH_5") (pintype "passive"))
      (node (ref "X2") (pin "2") (pinfunction "GND_2") (pintype "passive"))
      (node (ref "X2") (pin "4") (pinfunction "GND_4") (pintype "passive"))
    )
    (net (code "42") (name "Net-(C54-Pad1)") (class "Default")
      (node (ref "C54") (pin "1") (pinfunction "1_1") (pintype "passive"))
      (node (ref "R36") (pin "2") (pinfunction "2_2") (pintype "passive"))
    )
    (net (code "43") (name "Net-(D1-+)") (class "Default")
      (node (ref "D1") (pin "2") (pinfunction "+_2") (pintype "passive"))
      (node (ref "R11") (pin "1") (pinfunction "1_1") (pintype "passive"))
    )
    (net (code "44") (name "Net-(D2-+)") (class "Default")
      (node (ref "D2") (pin "2") (pinfunction "+_2") (pintype "passive"))
      (node (ref "R13") (pin "1") (pinfunction "1_1") (pintype "passive"))
    )
    (net (code "45") (name "Net-(D3-+)") (class "Default")
      (node (ref "D3") (pin "2") (pinfunction "+_2") (pintype "passive"))
      (node (ref "R14") (pin "1") (pinfunction "1_1") (pintype "passive"))
    )
    (net (code "46") (name "Net-(D4-+)") (class "Default")
      (node (ref "D4") (pin "2") (pinfunction "+_2") (pintype "passive"))
      (node (ref "R15") (pin "1") (pinfunction "1_1") (pintype "passive"))
    )
    (net (code "47") (name "Net-(L4-ANT)") (class "Default")
      (node (ref "L4") (pin "1") (pinfunction "ANT_1") (pintype "passive"))
      (node (ref "U8") (pin "2") (pinfunction "WIFI/BT_ANT_2") (pintype "passive"))
    )
    (net (code "48") (name "Net-(U1-FB)") (class "Default")
      (node (ref "R2") (pin "1") (pinfunction "1_1") (pintype "passive"))
      (node (ref "R3") (pin "2") (pinfunction "2_2") (pintype "passive"))
      (node (ref "U1") (pin "5") (pinfunction "FB_5") (pintype "passive"))
    )
    (net (code "49") (name "Net-(U1-LX)") (class "Default")
      (node (ref "L1") (pin "2") (pinfunction "2_2") (pintype "passive"))
      (node (ref "U1") (pin "3") (pinfunction "LX_3") (pintype "passive"))
    )
    (net (code "50") (name "Net-(U2-EPHY-RTX)") (class "Default")
      (node (ref "R6") (pin "2") (pinfunction "2_2") (pintype "passive"))
      (node (ref "U2") (pin "94") (pinfunction "EPHY-RTX_94") (pintype "passive"))
    )
    (net (code "51") (name "Net-(U2-HBIAS)") (class "Default")
      (node (ref "C13") (pin "1") (pinfunction "1_1") (pintype "passive"))
      (node (ref "U2") (pin "119") (pinfunction "HBIAS_119") (pintype "passive"))
    )
    (net (code "52") (name "Net-(U2-HPVCCBP)") (class "Default")
      (node (ref "C11") (pin "2") (pinfunction "2_2") (pintype "passive"))
      (node (ref "C12") (pin "2") (pinfunction "2_2") (pintype "passive"))
      (node (ref "U2") (pin "123") (pinfunction "HPVCCBP_123") (pintype "passive"))
    )
    (net (code "53") (name "Net-(U2-PF6)") (class "Default")
      (node (ref "R4") (pin "1") (pinfunction "1_1") (pintype "passive"))
      (node (ref "U2") (pin "100") (pinfunction "PF6_100") (pintype "passive"))
    )
    (net (code "54") (name "Net-(U2-RTC-VIO)") (class "Default")
      (node (ref "C14") (pin "1") (pinfunction "1_1") (pintype "passive"))
      (node (ref "U2") (pin "97") (pinfunction "RTC-VIO_97") (pintype "passive"))
    )
    (net (code "55") (name "Net-(U2-SZQ)") (class "Default")
      (node (ref "R12") (pin "2") (pinfunction "2_2") (pintype "passive"))
      (node (ref "U2") (pin "73") (pinfunction "SZQ_73") (pintype "passive"))
    )
    (net (code "56") (name "Net-(U2-VRA1)") (class "Default")
      (node (ref "C1") (pin "1") (pinfunction "1_1") (pintype "passive"))
      (node (ref "U2") (pin "117") (pinfunction "VRA1_117") (pintype "passive"))
    )
    (net (code "57") (name "Net-(U2-VRA2)") (class "Default")
      (node (ref "C2") (pin "1") (pinfunction "1_1") (pintype "passive"))
      (node (ref "R1") (pin "1") (pinfunction "1_1") (pintype "passive"))
      (node (ref "U2") (pin "118") (pinfunction "VRA2_118") (pintype "passive"))
    )
    (net (code "58") (name "Net-(U2-X24MIN)") (class "Default")
      (node (ref "C37") (pin "1") (pinfunction "1_1") (pintype "passive"))
      (node (ref "U2") (pin "75") (pinfunction "X24MIN_75") (pintype "passive"))
      (node (ref "X2") (pin "3") (pinfunction "OSC2_3") (pintype "passive"))
    )
    (net (code "59") (name "Net-(U2-X24MOUT)") (class "Default")
      (node (ref "C40") (pin "1") (pinfunction "1_1") (pintype "passive"))
      (node (ref "U2") (pin "74") (pinfunction "X24MOUT_74") (pintype "passive"))
      (node (ref "X2") (pin "1") (pinfunction "OSC1_1") (pintype "passive"))
    )
    (net (code "60") (name "Net-(U2-X32KIN)") (class "Default")
      (node (ref "C23") (pin "1") (pinfunction "1_1") (pintype "passive"))
      (node (ref "U2") (pin "96") (pinfunction "X32KIN_96") (pintype "passive"))
      (node (ref "X1") (pin "2") (pinfunction "OSC2_2") (pintype "passive"))
    )
    (net (code "61") (name "Net-(U2-X32KOUT)") (class "Default")
      (node (ref "C24") (pin "1") (pinfunction "1_1") (pintype "passive"))
      (node (ref "U2") (pin "95") (pinfunction "X32KOUT_95") (pintype "passive"))
      (node (ref "X1") (pin "1") (pinfunction "OSC1_1") (pintype "passive"))
    )
    (net (code "62") (name "Net-(U3-FB)") (class "Default")
      (node (ref "R7") (pin "1") (pinfunction "1_1") (pintype "passive"))
      (node (ref "R8") (pin "2") (pinfunction "2_2") (pintype "passive"))
      (node (ref "U3") (pin "5") (pinfunction "FB_5") (pintype "passive"))
    )
    (net (code "63") (name "Net-(U3-LX)") (class "Default")
      (node (ref "L2") (pin "2") (pinfunction "2_2") (pintype "passive"))
      (node (ref "U3") (pin "3") (pinfunction "LX_3") (pintype "passive"))
    )
    (net (code "64") (name "Net-(U4-FB)") (class "Default")
      (node (ref "R10") (pin "2") (pinfunction "2_2") (pintype "passive"))
      (node (ref "R9") (pin "1") (pinfunction "1_1") (pintype "passive"))
      (node (ref "U4") (pin "5") (pinfunction "FB_5") (pintype "passive"))
    )
    (net (code "65") (name "Net-(U4-LX)") (class "Default")
      (node (ref "L3") (pin "2") (pinfunction "2_2") (pintype "passive"))
      (node (ref "U4") (pin "3") (pinfunction "LX_3") (pintype "passive"))
    )
    (net (code "66") (name "Net-(U6-V3)") (class "Default")
      (node (ref "C47") (pin "1") (pinfunction "1_1") (pintype "passive"))
      (node (ref "U6") (pin "10") (pinfunction "V3_10") (pintype "passive"))
    )
    (net (code "67") (name "Net-(U8-BT_RST)") (class "Default")
      (node (ref "R35") (pin "2") (pinfunction "2_2") (pintype "passive"))
      (node (ref "U8") (pin "34") (pinfunction "BT_RST_34") (pintype "passive"))
    )
    (net (code "68") (name "Net-(U8-WL_H_WK)") (class "Default")
      (node (ref "R33") (pin "2") (pinfunction "2_2") (pintype "passive"))
      (node (ref "U8") (pin "13") (pinfunction "WL_H_WK_13") (pintype "passive"))
    )
    (net (code "69") (name "Net-(U8-WL_REG)") (class "Default")
      (node (ref "R34") (pin "2") (pinfunction "2_2") (pintype "passive"))
      (node (ref "U8") (pin "12") (pinfunction "WL_REG_12") (pintype "passive"))
    )
    (net (code "70") (name "unconnected-(L4-Pad2)") (class "Default")
      (node (ref "L4") (pin "2") (pinfunction "2_2") (pintype "passive+no_connect"))
    )
    (net (code "71") (name "unconnected-(TF1-CD-Pad9)") (class "Default")
      (node (ref "TF1") (pin "9") (pinfunction "CD_9") (pintype "passive+no_connect"))
    )
    (net (code "72") (name "unconnected-(U2-EPHY-LINK-LED-Pad77)") (class "Default")
      (node (ref "U2") (pin "77") (pinfunction "EPHY-LINK-LED_77") (pintype "passive+no_connect"))
    )
    (net (code "73") (name "unconnected-(U2-EPHY-RXN-Pad89)") (class "Default")
      (node (ref "U2") (pin "89") (pinfunction "EPHY-RXN_89") (pintype "passive+no_connect"))
    )
    (net (code "74") (name "unconnected-(U2-EPHY-RXP-Pad90)") (class "Default")
      (node (ref "U2") (pin "90") (pinfunction "EPHY-RXP_90") (pintype "passive+no_connect"))
    )
    (net (code "75") (name "unconnected-(U2-EPHY-SPD-LED-Pad78)") (class "Default")
      (node (ref "U2") (pin "78") (pinfunction "EPHY-SPD-LED_78") (pintype "passive+no_connect"))
    )
    (net (code "76") (name "unconnected-(U2-EPHY-TXN-Pad91)") (class "Default")
      (node (ref "U2") (pin "91") (pinfunction "EPHY-TXN_91") (pintype "passive+no_connect"))
    )
    (net (code "77") (name "unconnected-(U2-EPHY-TXP-Pad92)") (class "Default")
      (node (ref "U2") (pin "92") (pinfunction "EPHY-TXP_92") (pintype "passive+no_connect"))
    )
    (net (code "78") (name "unconnected-(U2-LRADC0-Pad112)") (class "Default")
      (node (ref "U2") (pin "112") (pinfunction "LRADC0_112") (pintype "passive+no_connect"))
    )
    (net (code "79") (name "unconnected-(U2-MCSI-CKN-Pad87)") (class "Default")
      (node (ref "U2") (pin "87") (pinfunction "MCSI-CKN_87") (pintype "passive+no_connect"))
    )
    (net (code "80") (name "unconnected-(U2-MCSI-CKP-Pad86)") (class "Default")
      (node (ref "U2") (pin "86") (pinfunction "MCSI-CKP_86") (pintype "passive+no_connect"))
    )
    (net (code "81") (name "unconnected-(U2-MCSI-D0N-Pad82)") (class "Default")
      (node (ref "U2") (pin "82") (pinfunction "MCSI-D0N_82") (pintype "passive+no_connect"))
    )
    (net (code "82") (name "unconnected-(U2-MCSI-D0P-Pad81)") (class "Default")
      (node (ref "U2") (pin "81") (pinfunction "MCSI-D0P_81") (pintype "passive+no_connect"))
    )
    (net (code "83") (name "unconnected-(U2-MCSI-D1N-Pad84)") (class "Default")
      (node (ref "U2") (pin "84") (pinfunction "MCSI-D1N_84") (pintype "passive+no_connect"))
    )
    (net (code "84") (name "unconnected-(U2-MCSI-D1P-Pad83)") (class "Default")
      (node (ref "U2") (pin "83") (pinfunction "MCSI-D1P_83") (pintype "passive+no_connect"))
    )
    (net (code "85") (name "unconnected-(U2-MICIN1N-Pad114)") (class "Default")
      (node (ref "U2") (pin "114") (pinfunction "MICIN1N_114") (pintype "passive+no_connect"))
    )
    (net (code "86") (name "unconnected-(U2-MICIN1P-Pad113)") (class "Default")
      (node (ref "U2") (pin "113") (pinfunction "MICIN1P_113") (pintype "passive+no_connect"))
    )
    (net (code "87") (name "unconnected-(U2-PB2{slash}UART2_RTS{slash}PB_EINT2-Pad41)") (class "Default")
      (node (ref "U2") (pin "41") (pinfunction "PB2/UART2_RTS/PB_EINT2_41") (pintype "passive+no_connect"))
    )
    (net (code "88") (name "unconnected-(U2-PB3{slash}UART2_CTS{slash}PB_EINT3-Pad42)") (class "Default")
      (node (ref "U2") (pin "42") (pinfunction "PB3/UART2_CTS/PB_EINT3_42") (pintype "passive+no_connect"))
    )
    (net (code "89") (name "unconnected-(U2-PB6{slash}TWI0_SCK{slash}PB_EINT6-Pad45)") (class "Default")
      (node (ref "U2") (pin "45") (pinfunction "PB6/TWI0_SCK/PB_EINT6_45") (pintype "passive+no_connect"))
    )
    (net (code "90") (name "unconnected-(U2-PB7{slash}TWI0_SDA{slash}PB_EINT7-Pad46)") (class "Default")
      (node (ref "U2") (pin "46") (pinfunction "PB7/TWI0_SDA/PB_EINT7_46") (pintype "passive+no_connect"))
    )
    (net (code "91") (name "unconnected-(U2-PC0{slash}SDC2_CLK{slash}SPI_MISO-Pad52)") (class "Default")
      (node (ref "U2") (pin "52") (pinfunction "PC0/SDC2_CLK/SPI_MISO_52") (pintype "passive+no_connect"))
    )
    (net (code "92") (name "unconnected-(U2-PE0{slash}CSI_PCLK{slash}LCD_CLK-Pad37)") (class "Default")
      (node (ref "U2") (pin "37") (pinfunction "PE0/CSI_PCLK/LCD_CLK_37") (pintype "passive+no_connect"))
    )
    (net (code "93") (name "unconnected-(U2-PE1{slash}CSI_MCLK{slash}LCD_DE-Pad36)") (class "Default")
      (node (ref "U2") (pin "36") (pinfunction "PE1/CSI_MCLK/LCD_DE_36") (pintype "passive+no_connect"))
    )
    (net (code "94") (name "unconnected-(U2-PE2{slash}CSI_HSYNC{slash}LCD_HSYNC-Pad35)") (class "Default")
      (node (ref "U2") (pin "35") (pinfunction "PE2/CSI_HSYNC/LCD_HSYNC_35") (pintype "passive+no_connect"))
    )
    (net (code "95") (name "unconnected-(U2-PE3{slash}CSI_VSYNC{slash}LCD_VSYNC-Pad34)") (class "Default")
      (node (ref "U2") (pin "34") (pinfunction "PE3/CSI_VSYNC/LCD_VSYNC_34") (pintype "passive+no_connect"))
    )
    (net (code "96") (name "unconnected-(U2-PE4{slash}CSI_D0{slash}LCD_D2-Pad33)") (class "Default")
      (node (ref "U2") (pin "33") (pinfunction "PE4/CSI_D0/LCD_D2_33") (pintype "passive+no_connect"))
    )
    (net (code "97") (name "unconnected-(U2-PE5{slash}CSI_D1{slash}LCD_D3-Pad32)") (class "Default")
      (node (ref "U2") (pin "32") (pinfunction "PE5/CSI_D1/LCD_D3_32") (pintype "passive+no_connect"))
    )
    (net (code "98") (name "unconnected-(U2-PE6{slash}CSI_D2{slash}LCD_D4-Pad31)") (class "Default")
      (node (ref "U2") (pin "31") (pinfunction "PE6/CSI_D2/LCD_D4_31") (pintype "passive+no_connect"))
    )
    (net (code "99") (name "unconnected-(U2-PE7{slash}CSI_D3{slash}LCD_D5-Pad30)") (class "Default")
      (node (ref "U2") (pin "30") (pinfunction "PE7/CSI_D3/LCD_D5_30") (pintype "passive+no_connect"))
    )
    (net (code "100") (name "unconnected-(U2-PE8{slash}CSI_D4{slash}LCD_D6-Pad28)") (class "Default")
      (node (ref "U2") (pin "28") (pinfunction "PE8/CSI_D4/LCD_D6_28") (pintype "passive+no_connect"))
    )
    (net (code "101") (name "unconnected-(U2-PE9{slash}CSI_D5{slash}LCD_D7-Pad27)") (class "Default")
      (node (ref "U2") (pin "27") (pinfunction "PE9/CSI_D5/LCD_D7_27") (pintype "passive+no_connect"))
    )
    (net (code "102") (name "unconnected-(U2-PE10{slash}CSI_D6{slash}LCD_D10-Pad24)") (class "Default")
      (node (ref "U2") (pin "24") (pinfunction "PE10/CSI_D6/LCD_D10_24") (pintype "passive+no_connect"))
    )
    (net (code "103") (name "unconnected-(U2-PE11{slash}CSI_D7{slash}LCD_D11-Pad23)") (class "Default")
      (node (ref "U2") (pin "23") (pinfunction "PE11/CSI_D7/LCD_D11_23") (pintype "passive+no_connect"))
    )
    (net (code "104") (name "unconnected-(U2-PE12{slash}CSI_D8{slash}LCD_D12-Pad22)") (class "Default")
      (node (ref "U2") (pin "22") (pinfunction "PE12/CSI_D8/LCD_D12_22") (pintype "passive+no_connect"))
    )
    (net (code "105") (name "unconnected-(U2-PE13{slash}CSI_D9{slash}LCD_D13-Pad18)") (class "Default")
      (node (ref "U2") (pin "18") (pinfunction "PE13/CSI_D9/LCD_D13_18") (pintype "passive+no_connect"))
    )
    (net (code "106") (name "unconnected-(U2-PE14{slash}CSI_D10{slash}LCD_D14-Pad17)") (class "Default")
      (node (ref "U2") (pin "17") (pinfunction "PE14/CSI_D10/LCD_D14_17") (pintype "passive+no_connect"))
    )
    (net (code "107") (name "unconnected-(U2-PE15{slash}CSI_D11{slash}LCD_D15-Pad16)") (class "Default")
      (node (ref "U2") (pin "16") (pinfunction "PE15/CSI_D11/LCD_D15_16") (pintype "passive+no_connect"))
    )
    (net (code "108") (name "unconnected-(U2-PE16{slash}CSI_D12{slash}LCD_D18-Pad15)") (class "Default")
      (node (ref "U2") (pin "15") (pinfunction "PE16/CSI_D12/LCD_D18_15") (pintype "passive+no_connect"))
    )
    (net (code "109") (name "unconnected-(U2-PE17{slash}CSI_D13{slash}LCD_D19-Pad14)") (class "Default")
      (node (ref "U2") (pin "14") (pinfunction "PE17/CSI_D13/LCD_D19_14") (pintype "passive+no_connect"))
    )
    (net (code "110") (name "unconnected-(U2-PE18{slash}CSI_D14{slash}LCD_D20-Pad13)") (class "Default")
      (node (ref "U2") (pin "13") (pinfunction "PE18/CSI_D14/LCD_D20_13") (pintype "passive+no_connect"))
    )
    (net (code "111") (name "unconnected-(U2-PE19{slash}CSI_D15{slash}LCD_D21-Pad11)") (class "Default")
      (node (ref "U2") (pin "11") (pinfunction "PE19/CSI_D15/LCD_D21_11") (pintype "passive+no_connect"))
    )
    (net (code "112") (name "unconnected-(U2-PE20{slash}CSI_FIELD{slash}CSI_MIPI_MCLK-Pad10)") (class "Default")
      (node (ref "U2") (pin "10") (pinfunction "PE20/CSI_FIELD/CSI_MIPI_MCLK_10") (pintype "passive+no_connect"))
    )
    (net (code "113") (name "unconnected-(U2-PE21{slash}CSI_SCK{slash}TWI1_SCK{slash}UART1_TX-Pad9)") (class "Default")
      (node (ref "U2") (pin "9") (pinfunction "PE21/CSI_SCK/TWI1_SCK/UART1_TX_9") (pintype "passive+no_connect"))
    )
    (net (code "114") (name "unconnected-(U6-CTS#-Pad5)") (class "Default")
      (node (ref "U6") (pin "5") (pinfunction "CTS#_5") (pintype "passive+no_connect"))
    )
    (net (code "115") (name "unconnected-(U6-RTS#-Pad4)") (class "Default")
      (node (ref "U6") (pin "4") (pinfunction "RTS#_4") (pintype "passive+no_connect"))
    )
    (net (code "116") (name "unconnected-(U6-TNOW-Pad6)") (class "Default")
      (node (ref "U6") (pin "6") (pinfunction "TNOW_6") (pintype "passive+no_connect"))
    )
    (net (code "117") (name "unconnected-(U7-CC1-PadA5)") (class "Default")
      (node (ref "U7") (pin "A5") (pinfunction "CC1_A5") (pintype "passive+no_connect"))
    )
    (net (code "118") (name "unconnected-(U7-CC2-PadB5)") (class "Default")
      (node (ref "U7") (pin "B5") (pinfunction "CC2_B5") (pintype "passive+no_connect"))
    )
    (net (code "119") (name "unconnected-(U7-SBU1-PadA8)") (class "Default")
      (node (ref "U7") (pin "A8") (pinfunction "SBU1_A8") (pintype "passive+no_connect"))
    )
    (net (code "120") (name "unconnected-(U7-SBU2-PadB8)") (class "Default")
      (node (ref "U7") (pin "B8") (pinfunction "SBU2_B8") (pintype "passive+no_connect"))
    )
    (net (code "121") (name "unconnected-(U8-BT_H_WK-Pad7)") (class "Default")
      (node (ref "U8") (pin "7") (pinfunction "BT_H_WK_7") (pintype "passive+no_connect"))
    )
    (net (code "122") (name "unconnected-(U8-BT_WK-Pad6)") (class "Default")
      (node (ref "U8") (pin "6") (pinfunction "BT_WK_6") (pintype "passive+no_connect"))
    )
    (net (code "123") (name "unconnected-(U8-BT_XTAL_IN-Pad37)") (class "Default")
      (node (ref "U8") (pin "37") (pinfunction "BT_XTAL_IN_37") (pintype "passive+no_connect"))
    )
    (net (code "124") (name "unconnected-(U8-BT_XTAL_OUT-Pad38)") (class "Default")
      (node (ref "U8") (pin "38") (pinfunction "BT_XTAL_OUT_38") (pintype "passive+no_connect"))
    )
    (net (code "125") (name "unconnected-(U8-LPO-Pad24)") (class "Default")
      (node (ref "U8") (pin "24") (pinfunction "LPO_24") (pintype "passive+no_connect"))
    )
    (net (code "126") (name "unconnected-(U8-NC-Pad4)") (class "Default")
      (node (ref "U8") (pin "4") (pinfunction "NC_4") (pintype "passive+no_connect"))
    )
    (net (code "127") (name "unconnected-(U8-NC-Pad5)") (class "Default")
      (node (ref "U8") (pin "5") (pinfunction "NC_5") (pintype "passive+no_connect"))
    )
    (net (code "128") (name "unconnected-(U8-NC-Pad8)") (class "Default")
      (node (ref "U8") (pin "8") (pinfunction "NC_8") (pintype "passive+no_connect"))
    )
    (net (code "129") (name "unconnected-(U8-NC-Pad32)") (class "Default")
      (node (ref "U8") (pin "32") (pinfunction "NC_32") (pintype "passive+no_connect"))
    )
    (net (code "130") (name "unconnected-(U8-NC-Pad35)") (class "Default")
      (node (ref "U8") (pin "35") (pinfunction "NC_35") (pintype "passive+no_connect"))
    )
    (net (code "131") (name "unconnected-(U8-NC-Pad39)") (class "Default")
      (node (ref "U8") (pin "39") (pinfunction "NC_39") (pintype "passive+no_connect"))
    )
    (net (code "132") (name "unconnected-(U8-NC-Pad40)") (class "Default")
      (node (ref "U8") (pin "40") (pinfunction "NC_40") (pintype "passive+no_connect"))
    )
    (net (code "133") (name "unconnected-(U8-PCM_CLK-Pad26)") (class "Default")
      (node (ref "U8") (pin "26") (pinfunction "PCM_CLK_26") (pintype "passive+no_connect"))
    )
    (net (code "134") (name "unconnected-(U8-PCM_IN-Pad27)") (class "Default")
      (node (ref "U8") (pin "27") (pinfunction "PCM_IN_27") (pintype "passive+no_connect"))
    )
    (net (code "135") (name "unconnected-(U8-PCM_OUT-Pad25)") (class "Default")
      (node (ref "U8") (pin "25") (pinfunction "PCM_OUT_25") (pintype "passive+no_connect"))
    )
    (net (code "136") (name "unconnected-(U8-PCM_SYNC-Pad28)") (class "Default")
      (node (ref "U8") (pin "28") (pinfunction "PCM_SYNC_28") (pintype "passive+no_connect"))
    )
    (net (code "137") (name "unconnected-(U8-TCXO_IN-Pad30)") (class "Default")
      (node (ref "U8") (pin "30") (pinfunction "TCXO_IN_30") (pintype "passive+no_connect"))
    )
    (net (code "138") (name "unconnected-(U8-VDD_TXCO-Pad29)") (class "Default")
      (node (ref "U8") (pin "29") (pinfunction "VDD_TXCO_29") (pintype "passive+no_connect"))
    )
    (net (code "139") (name "unconnected-(U8-VIN_LDO-Pad23)") (class "Default")
      (node (ref "U8") (pin "23") (pinfunction "VIN_LDO_23") (pintype "passive+no_connect"))
    )
    (net (code "140") (name "unconnected-(U8-VIN_LDO_OUT-Pad21)") (class "Default")
      (node (ref "U8") (pin "21") (pinfunction "VIN_LDO_OUT_21") (pintype "passive+no_connect"))
    )
    (net (code "141") (name "unconnected-(U8-WL_XTAL_IN-Pad10)") (class "Default")
      (node (ref "U8") (pin "10") (pinfunction "WL_XTAL_IN_10") (pintype "passive+no_connect"))
    )
    (net (code "142") (name "unconnected-(U8-WL_XTAL_OUT-Pad11)") (class "Default")
      (node (ref "U8") (pin "11") (pinfunction "WL_XTAL_OUT_11") (pintype "passive+no_connect"))
    )
  )
)
